# CD.net
KiCad netlist of a schematic drawn in EAGLE
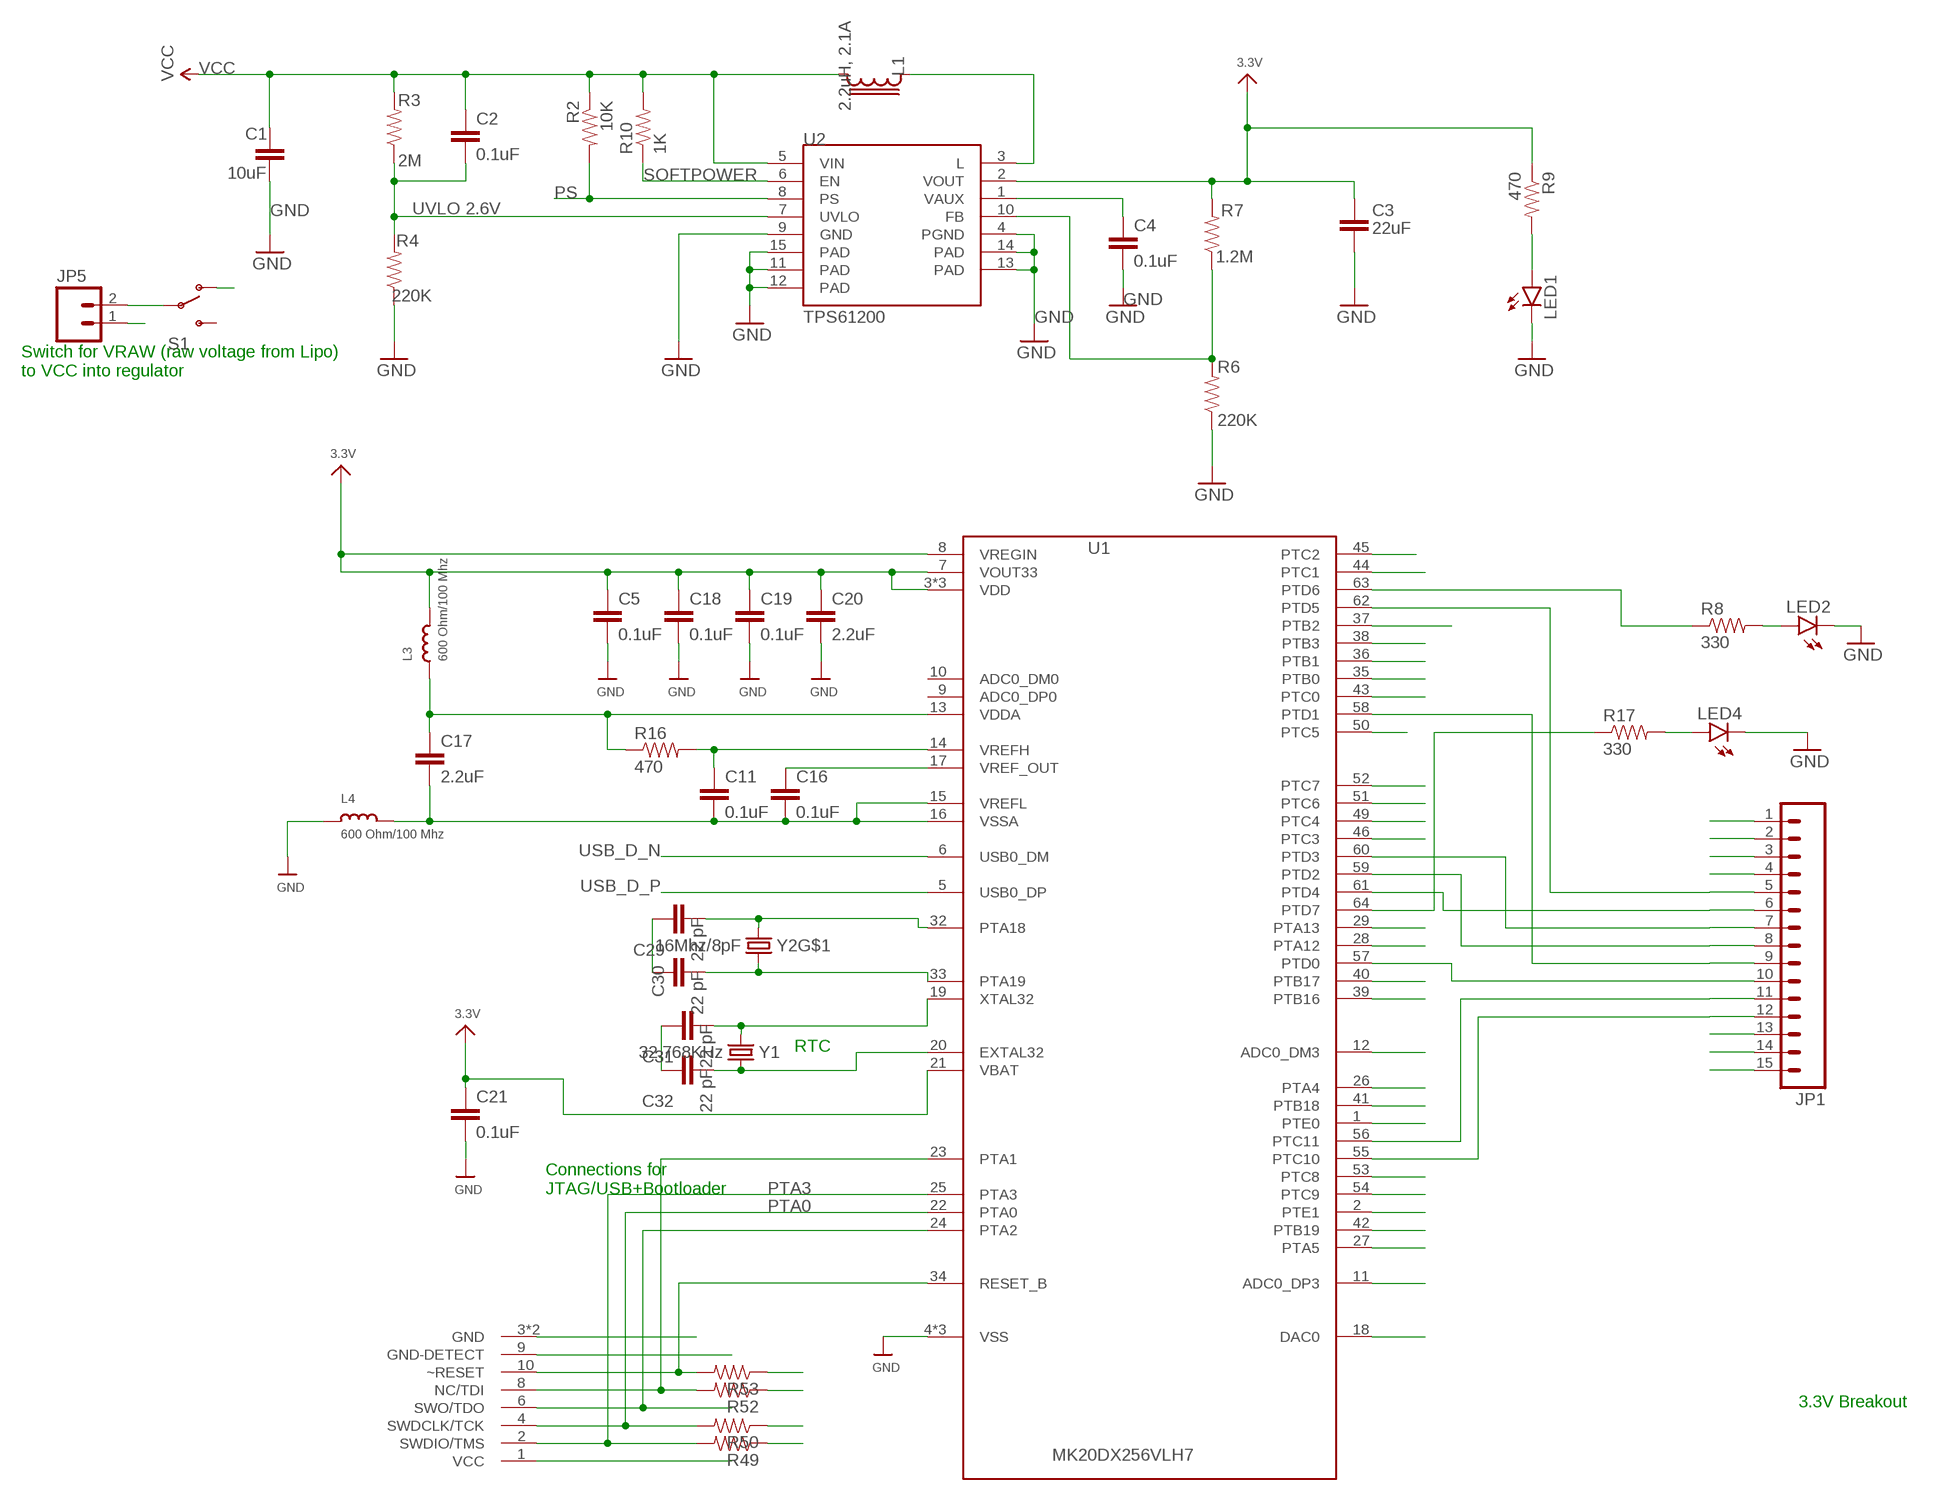
[diagram p0: schematic, sheet 1]
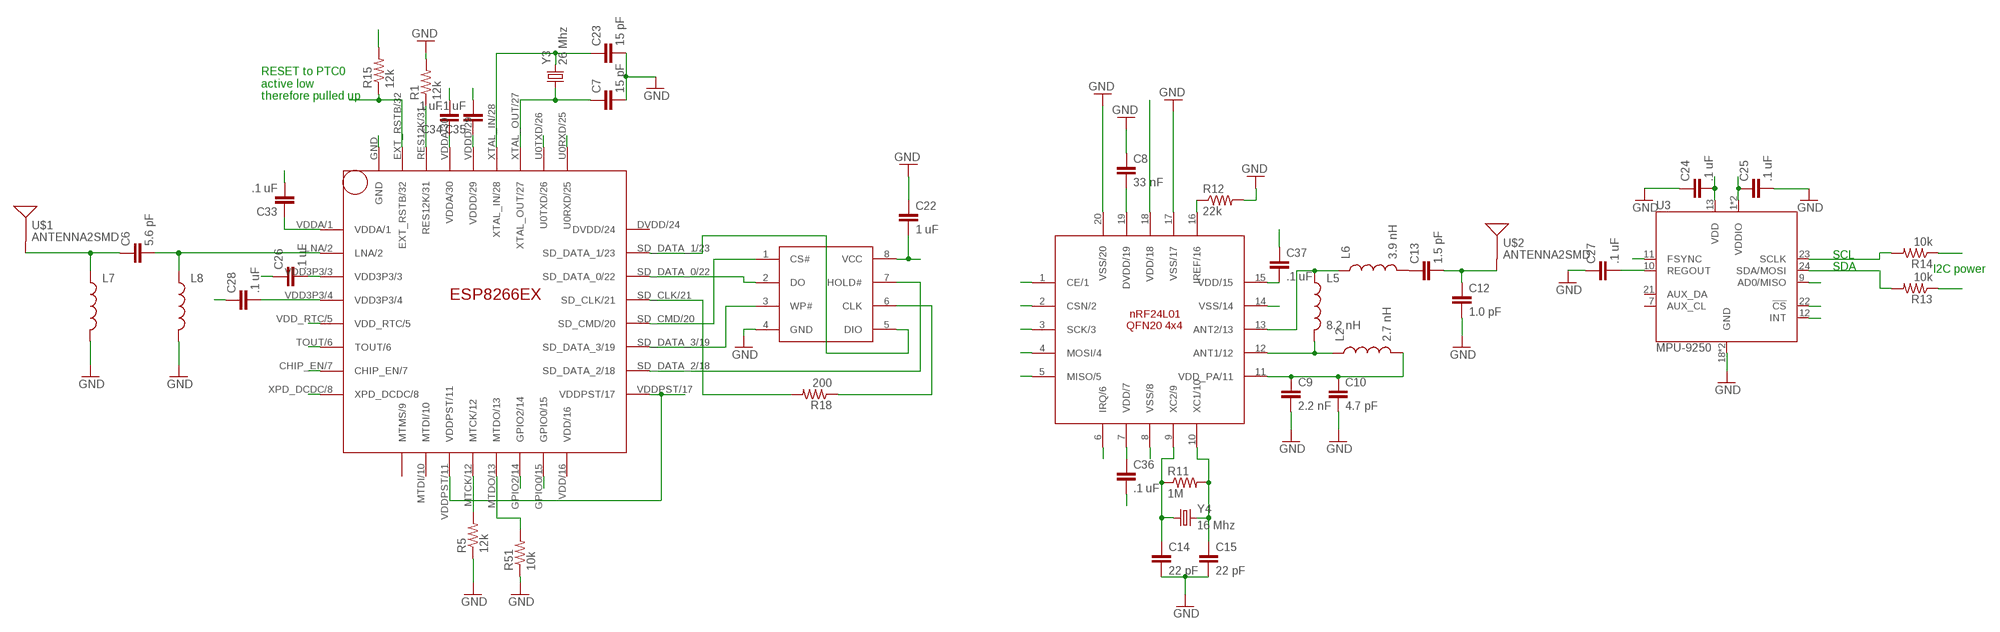
[diagram p1: schematic, sheet 2]
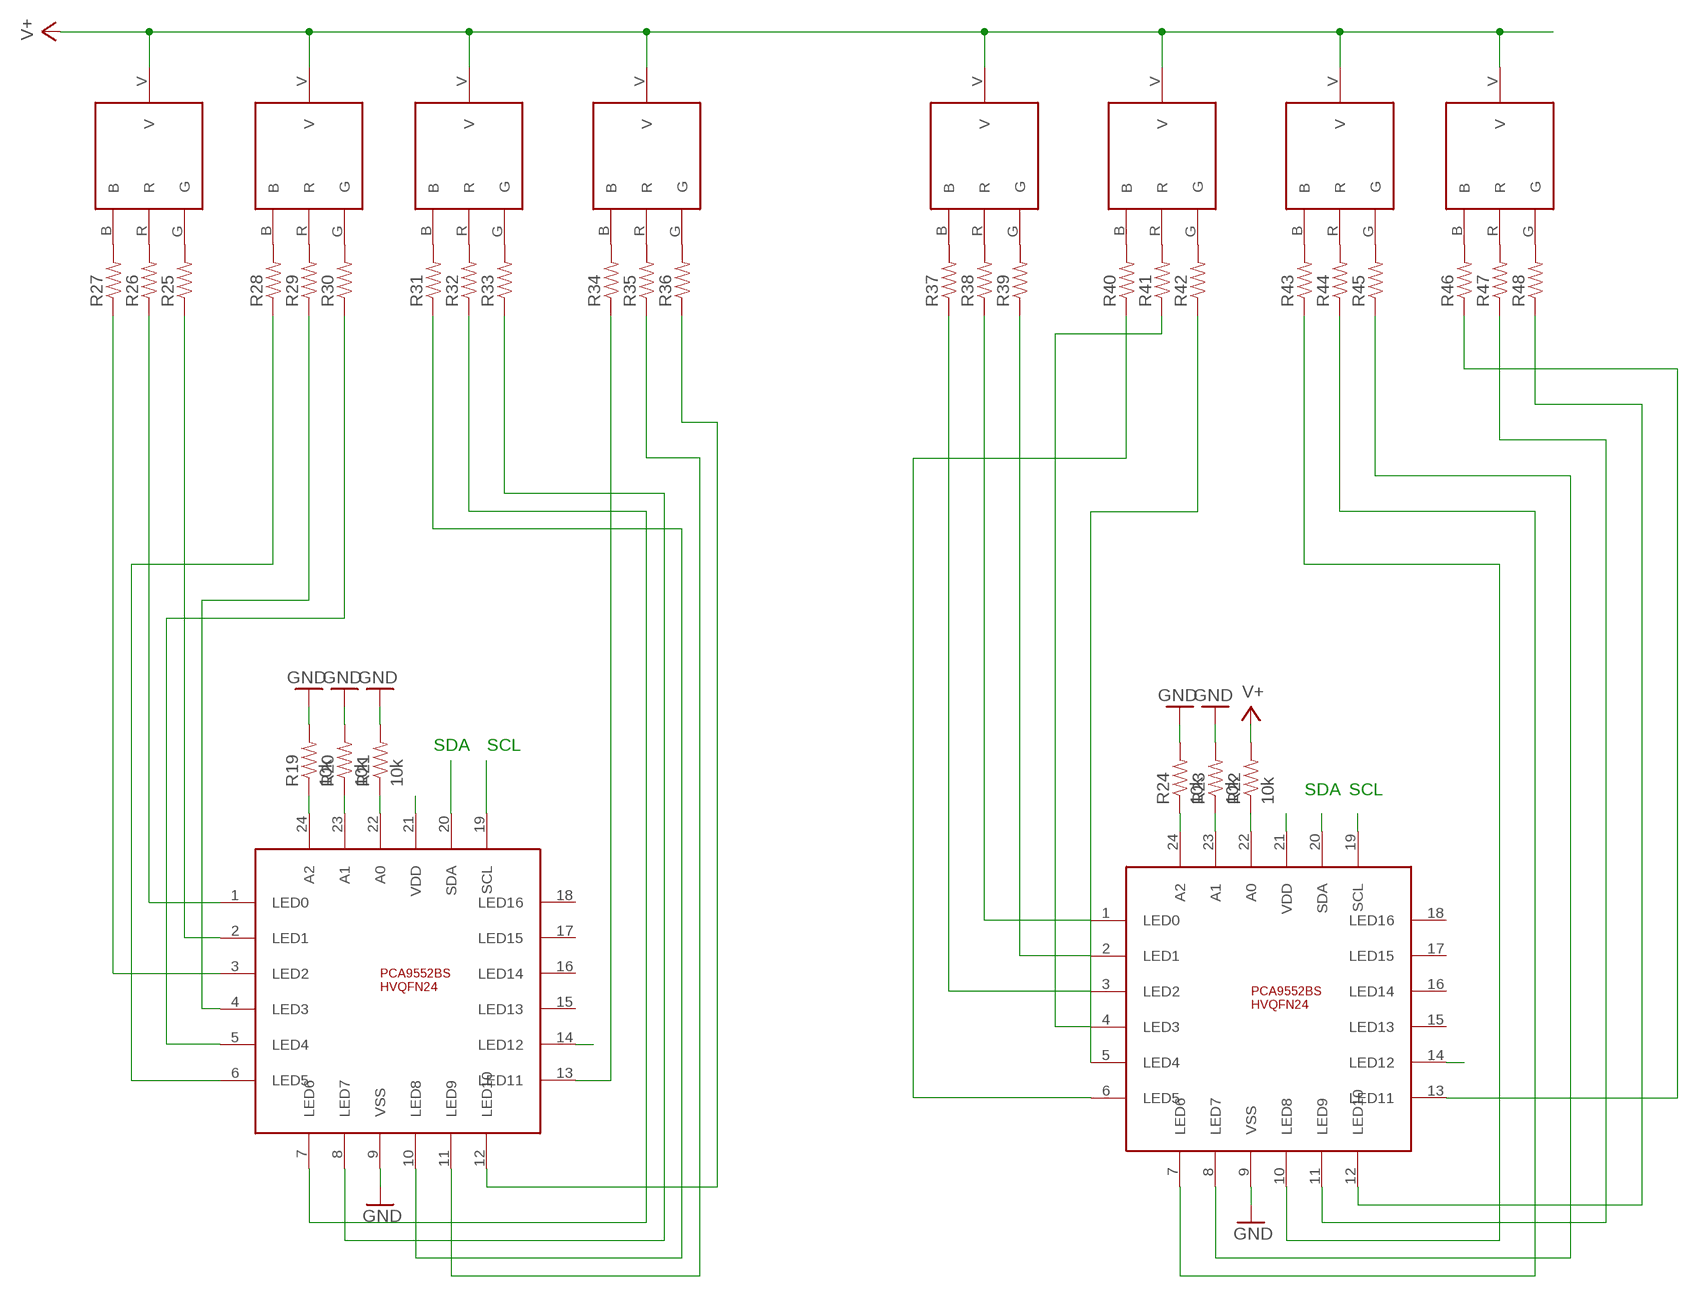
[diagram p2: schematic, sheet 3]

(export (version "E")
  (design (tool "Eeschema 10.0.6"))
  (components
    (comp (ref "C1")
      (value "10uF")
      (footprint "eagle-import:0603-CAP")
      (fields (field (name "MF") "Murata") (field (name "MPN") "GRM188R60J106ME47D"))
      (libsource (lib "eagle-import") (part "CAPACITOR-10UF"))
    )
    (comp (ref "C2")
      (value "0.1uF")
      (footprint "eagle-import:0603-CAP")
      (fields (field (name "MF") "Kemet") (field (name "MPN") "C0603C104J3RACTU"))
      (libsource (lib "eagle-import") (part "CAPACITOR-0.1UF"))
    )
    (comp (ref "C3")
      (value "22uF")
      (footprint "eagle-import:0603-CAP")
      (fields (field (name "MF") "Murata") (field (name "MPN") "GRM188R60J226MEA0D"))
      (libsource (lib "eagle-import") (part "CAPACITOR-22UF"))
    )
    (comp (ref "C4")
      (value "0.1uF")
      (footprint "eagle-import:0603-CAP")
      (fields (field (name "MF") "Kemet") (field (name "MPN") "C0603C104J3RACTU"))
      (libsource (lib "eagle-import") (part "CAPACITOR-0.1UF"))
    )
    (comp (ref "C5")
      (value "0.1uF")
      (footprint "eagle-import:0603-CAP")
      (fields (field (name "MF") "Kemet") (field (name "MPN") "C0603C104J3RACTU"))
      (libsource (lib "eagle-import") (part "CAPACITOR-0.1UF"))
    )
    (comp (ref "C11")
      (value "0.1uF")
      (footprint "eagle-import:0603-CAP")
      (fields (field (name "MF") "Kemet") (field (name "MPN") "C0603C104J3RACTU"))
      (libsource (lib "eagle-import") (part "CAPACITOR-0.1UF"))
    )
    (comp (ref "C16")
      (value "0.1uF")
      (footprint "eagle-import:0603-CAP")
      (fields (field (name "MF") "Kemet") (field (name "MPN") "C0603C104J3RACTU"))
      (libsource (lib "eagle-import") (part "CAPACITOR-0.1UF"))
    )
    (comp (ref "C17")
      (value "2.2uF")
      (footprint "eagle-import:0603-CAP")
      (fields (field (name "MF") "Kemet") (field (name "MPN") "C0603C225K4PACTU"))
      (libsource (lib "eagle-import") (part "CAPACITOR-2.2UF"))
    )
    (comp (ref "C18")
      (value "0.1uF")
      (footprint "eagle-import:0603-CAP")
      (fields (field (name "MF") "Kemet") (field (name "MPN") "C0603C104J3RACTU"))
      (libsource (lib "eagle-import") (part "CAPACITOR-0.1UF"))
    )
    (comp (ref "C19")
      (value "0.1uF")
      (footprint "eagle-import:0603-CAP")
      (fields (field (name "MF") "Kemet") (field (name "MPN") "C0603C104J3RACTU"))
      (libsource (lib "eagle-import") (part "CAPACITOR-0.1UF"))
    )
    (comp (ref "C20")
      (value "2.2uF")
      (footprint "eagle-import:0603-CAP")
      (fields (field (name "MF") "Kemet") (field (name "MPN") "C0603C225K4PACTU"))
      (libsource (lib "eagle-import") (part "CAPACITOR-2.2UF"))
    )
    (comp (ref "C21")
      (value "0.1uF")
      (footprint "eagle-import:0603-CAP")
      (fields (field (name "MF") "Kemet") (field (name "MPN") "C0603C104J3RACTU"))
      (libsource (lib "eagle-import") (part "CAPACITOR-0.1UF"))
    )
    (comp (ref "C29")
      (value "22 pF")
      (footprint "eagle-import:0603-CAP")
      (fields (field (name "MF") "Murata") (field (name "MPN") "GRM188R60J106ME47D"))
      (libsource (lib "eagle-import") (part "CAPACITOR-10UF"))
    )
    (comp (ref "C30")
      (value "22 pF")
      (footprint "eagle-import:0603-CAP")
      (fields (field (name "MF") "Murata") (field (name "MPN") "GRM188R60J106ME47D"))
      (libsource (lib "eagle-import") (part "CAPACITOR-10UF"))
    )
    (comp (ref "C31")
      (value "22 pF")
      (footprint "eagle-import:0603-CAP")
      (fields (field (name "MF") "Murata") (field (name "MPN") "GRM188R60J106ME47D"))
      (libsource (lib "eagle-import") (part "CAPACITOR-10UF"))
    )
    (comp (ref "C32")
      (value "22 pF")
      (footprint "eagle-import:0603-CAP")
      (fields (field (name "MF") "Murata") (field (name "MPN") "GRM188R60J106ME47D"))
      (libsource (lib "eagle-import") (part "CAPACITOR-10UF"))
    )
    (comp (ref "JP1")
      (value "M15")
      (footprint "eagle-import:1X15")
      (libsource (lib "eagle-import") (part "M15"))
    )
    (comp (ref "JP5")
      (value "M02PTH")
      (footprint "eagle-import:1X02")
      (libsource (lib "eagle-import") (part "M02PTH"))
    )
    (comp (ref "L1")
      (value "2.2uH, 2.1A")
      (footprint "eagle-import:LPS3015")
      (fields (field (name "MF") "Coilcraft") (field (name "MPN") "LPS3015-222MRB"))
      (libsource (lib "eagle-import") (part "LPS30152.2UH"))
    )
    (comp (ref "L3")
      (value "600 Ohm/100 Mhz")
      (footprint "eagle-import:0805")
      (fields (field (name "MF") "Taiyo Yuden") (field (name "MPN") "BK2125HM601-T"))
      (libsource (lib "eagle-import") (part "INDUCTOR-BK2125HM601-T"))
    )
    (comp (ref "L4")
      (value "600 Ohm/100 Mhz")
      (footprint "eagle-import:0805")
      (fields (field (name "MF") "Taiyo Yuden") (field (name "MPN") "BK2125HM601-T"))
      (libsource (lib "eagle-import") (part "INDUCTOR-BK2125HM601-T"))
    )
    (comp (ref "LED1")
      (value "LED-GREEN")
      (footprint "eagle-import:LED-0603")
      (fields (field (name "MF") "Avago") (field (name "MPN") "HSMG-C190"))
      (libsource (lib "eagle-import") (part "LED-GREEN"))
    )
    (comp (ref "LED2")
      (value "LED-GREEN")
      (footprint "eagle-import:LED-0603")
      (fields (field (name "MF") "Avago") (field (name "MPN") "HSMG-C190"))
      (libsource (lib "eagle-import") (part "LED-GREEN"))
    )
    (comp (ref "LED4")
      (value "LED-GREEN")
      (footprint "eagle-import:LED-0603")
      (fields (field (name "MF") "Avago") (field (name "MPN") "HSMG-C190"))
      (libsource (lib "eagle-import") (part "LED-GREEN"))
    )
    (comp (ref "R2")
      (value "10K")
      (footprint "eagle-import:0603-RES")
      (fields (field (name "MF") "Panasonic") (field (name "MPN") "ERJ-3GEYJ103V"))
      (libsource (lib "eagle-import") (part "RESISTOR-10K"))
    )
    (comp (ref "R3")
      (value "2M")
      (footprint "eagle-import:0603-RES")
      (fields (field (name "MF") "Panasonic") (field (name "MPN") "ERJ-3GEYJ205V"))
      (libsource (lib "eagle-import") (part "RESISTOR-2M"))
    )
    (comp (ref "R4")
      (value "220K")
      (footprint "eagle-import:0603-RES")
      (fields (field (name "MF") "Panasonic") (field (name "MPN") "ERJ-3GEYJ224V"))
      (libsource (lib "eagle-import") (part "RESISTOR-220K"))
    )
    (comp (ref "R6")
      (value "220K")
      (footprint "eagle-import:0603-RES")
      (fields (field (name "MF") "Panasonic") (field (name "MPN") "ERJ-3GEYJ224V"))
      (libsource (lib "eagle-import") (part "RESISTOR-220K"))
    )
    (comp (ref "R7")
      (value "1.2M")
      (footprint "eagle-import:0603-RES")
      (fields (field (name "MF") "Panasonic") (field (name "MPN") "ERJ-3GEYJ125V"))
      (libsource (lib "eagle-import") (part "RESISTOR-1.2M"))
    )
    (comp (ref "R8")
      (value "330")
      (footprint "eagle-import:0603-RES")
      (fields (field (name "MF") "Panasonic") (field (name "MPN") "ERJ-3GEYJ471V"))
      (libsource (lib "eagle-import") (part "RESISTOR-470"))
    )
    (comp (ref "R9")
      (value "470")
      (footprint "eagle-import:0603-RES")
      (fields (field (name "MF") "Panasonic") (field (name "MPN") "ERJ-3GEYJ471V"))
      (libsource (lib "eagle-import") (part "RESISTOR-470"))
    )
    (comp (ref "R10")
      (value "1K")
      (footprint "eagle-import:0603-RES")
      (fields (field (name "MF") "Panasonic") (field (name "MPN") "ERJ-3GEYJ102V"))
      (libsource (lib "eagle-import") (part "RESISTOR-1K"))
    )
    (comp (ref "R16")
      (value "470")
      (footprint "eagle-import:0603-RES")
      (fields (field (name "MF") "Panasonic") (field (name "MPN") "ERJ-3GEYJ471V"))
      (libsource (lib "eagle-import") (part "RESISTOR-470"))
    )
    (comp (ref "R17")
      (value "330")
      (footprint "eagle-import:0603-RES")
      (fields (field (name "MF") "Panasonic") (field (name "MPN") "ERJ-3GEYJ471V"))
      (libsource (lib "eagle-import") (part "RESISTOR-470"))
    )
    (comp (ref "R49")
      (value "RESISTOR0402-RES")
      (footprint "eagle-import:0402-RES")
      (libsource (lib "eagle-import") (part "RESISTOR0402-RES"))
    )
    (comp (ref "R50")
      (value "RESISTOR0402-RES")
      (footprint "eagle-import:0402-RES")
      (libsource (lib "eagle-import") (part "RESISTOR0402-RES"))
    )
    (comp (ref "R52")
      (value "RESISTOR0402-RES")
      (footprint "eagle-import:0402-RES")
      (libsource (lib "eagle-import") (part "RESISTOR0402-RES"))
    )
    (comp (ref "R53")
      (value "RESISTOR0402-RES")
      (footprint "eagle-import:0402-RES")
      (libsource (lib "eagle-import") (part "RESISTOR0402-RES"))
    )
    (comp (ref "S1")
      (value "SWITCH-SPDT-SMD-A")
      (footprint "eagle-import:SWITCH-SPST-SMD-A")
      (libsource (lib "eagle-import") (part "SWITCH-SPDT-SMD-A"))
    )
    (comp (ref "U$7")
      (value "2X5_0.05\"_CORTEX_DEBUGTH_NOKEY_UNSHROUDED")
      (footprint "eagle-import:2X5_0.05__TH_NS")
      (libsource (lib "eagle-import") (part "2X5_0.05{dblquote}_CORTEX_DEBUGTH_NOKEY_UNSHROUDED"))
    )
    (comp (ref "U1")
      (value "MK20DX256VLH7")
      (footprint "eagle-import:MK20DX256VLH7")
      (fields (field (name "MF") "Freescale"))
      (libsource (lib "eagle-import") (part "MK20DX256VLH7"))
    )
    (comp (ref "U2")
      (value "TPS61200")
      (footprint "eagle-import:QFN-10_PAD")
      (fields (field (name "MF") "Texas Instruments") (field (name "MPN") "TPS61200DRCR"))
      (libsource (lib "eagle-import") (part "TPS61200"))
    )
    (comp (ref "Y1")
      (value "32.768KHz")
      (footprint "eagle-import:CRYSTAL-TXC-7A")
      (fields (field (name "MF") "Epson Timing") (field (name "MPN") "FC-255 32.7680K-A3"))
      (libsource (lib "eagle-import") (part "CRYSTAL/32.768KHZ/SMD-TXC_7A"))
    )
    (comp (ref "Y2")
      (value "16Mhz/8pF")
      (footprint "eagle-import:CRYSTAL-SMD-5X3")
      (fields (field (name "MF") "ECS") (field (name "MPN") "ECS-160-8-30B-CKM"))
      (libsource (lib "eagle-import") (part "CRYSTAL/SMD-5X3-GND16MHZ/8PF"))
    )
    (comp (ref "R19")
      (value "10k")
      (footprint "eagle-import:0603-RES")
      (libsource (lib "eagle-import") (part "RESISTOR0603-RES"))
    )
    (comp (ref "R20")
      (value "10k")
      (footprint "eagle-import:0603-RES")
      (libsource (lib "eagle-import") (part "RESISTOR0603-RES"))
    )
    (comp (ref "R21")
      (value "10k")
      (footprint "eagle-import:0603-RES")
      (libsource (lib "eagle-import") (part "RESISTOR0603-RES"))
    )
    (comp (ref "R22")
      (value "10k")
      (footprint "eagle-import:0603-RES")
      (libsource (lib "eagle-import") (part "RESISTOR0603-RES"))
    )
    (comp (ref "R23")
      (value "10k")
      (footprint "eagle-import:0603-RES")
      (libsource (lib "eagle-import") (part "RESISTOR0603-RES"))
    )
    (comp (ref "R24")
      (value "10k")
      (footprint "eagle-import:0603-RES")
      (libsource (lib "eagle-import") (part "RESISTOR0603-RES"))
    )
    (comp (ref "R25")
      (value "RESISTOR0402-RES")
      (footprint "eagle-import:0402-RES")
      (libsource (lib "eagle-import") (part "RESISTOR0402-RES"))
    )
    (comp (ref "R26")
      (value "RESISTOR0402-RES")
      (footprint "eagle-import:0402-RES")
      (libsource (lib "eagle-import") (part "RESISTOR0402-RES"))
    )
    (comp (ref "R27")
      (value "RESISTOR0402-RES")
      (footprint "eagle-import:0402-RES")
      (libsource (lib "eagle-import") (part "RESISTOR0402-RES"))
    )
    (comp (ref "R28")
      (value "RESISTOR0402-RES")
      (footprint "eagle-import:0402-RES")
      (libsource (lib "eagle-import") (part "RESISTOR0402-RES"))
    )
    (comp (ref "R29")
      (value "RESISTOR0402-RES")
      (footprint "eagle-import:0402-RES")
      (libsource (lib "eagle-import") (part "RESISTOR0402-RES"))
    )
    (comp (ref "R30")
      (value "RESISTOR0402-RES")
      (footprint "eagle-import:0402-RES")
      (libsource (lib "eagle-import") (part "RESISTOR0402-RES"))
    )
    (comp (ref "R31")
      (value "RESISTOR0402-RES")
      (footprint "eagle-import:0402-RES")
      (libsource (lib "eagle-import") (part "RESISTOR0402-RES"))
    )
    (comp (ref "R32")
      (value "RESISTOR0402-RES")
      (footprint "eagle-import:0402-RES")
      (libsource (lib "eagle-import") (part "RESISTOR0402-RES"))
    )
    (comp (ref "R33")
      (value "RESISTOR0402-RES")
      (footprint "eagle-import:0402-RES")
      (libsource (lib "eagle-import") (part "RESISTOR0402-RES"))
    )
    (comp (ref "R34")
      (value "RESISTOR0402-RES")
      (footprint "eagle-import:0402-RES")
      (libsource (lib "eagle-import") (part "RESISTOR0402-RES"))
    )
    (comp (ref "R35")
      (value "RESISTOR0402-RES")
      (footprint "eagle-import:0402-RES")
      (libsource (lib "eagle-import") (part "RESISTOR0402-RES"))
    )
    (comp (ref "R36")
      (value "RESISTOR0402-RES")
      (footprint "eagle-import:0402-RES")
      (libsource (lib "eagle-import") (part "RESISTOR0402-RES"))
    )
    (comp (ref "R37")
      (value "RESISTOR0402-RES")
      (footprint "eagle-import:0402-RES")
      (libsource (lib "eagle-import") (part "RESISTOR0402-RES"))
    )
    (comp (ref "R38")
      (value "RESISTOR0402-RES")
      (footprint "eagle-import:0402-RES")
      (libsource (lib "eagle-import") (part "RESISTOR0402-RES"))
    )
    (comp (ref "R39")
      (value "RESISTOR0402-RES")
      (footprint "eagle-import:0402-RES")
      (libsource (lib "eagle-import") (part "RESISTOR0402-RES"))
    )
    (comp (ref "R40")
      (value "RESISTOR0402-RES")
      (footprint "eagle-import:0402-RES")
      (libsource (lib "eagle-import") (part "RESISTOR0402-RES"))
    )
    (comp (ref "R41")
      (value "RESISTOR0402-RES")
      (footprint "eagle-import:0402-RES")
      (libsource (lib "eagle-import") (part "RESISTOR0402-RES"))
    )
    (comp (ref "R42")
      (value "RESISTOR0402-RES")
      (footprint "eagle-import:0402-RES")
      (libsource (lib "eagle-import") (part "RESISTOR0402-RES"))
    )
    (comp (ref "R43")
      (value "RESISTOR0402-RES")
      (footprint "eagle-import:0402-RES")
      (libsource (lib "eagle-import") (part "RESISTOR0402-RES"))
    )
    (comp (ref "R44")
      (value "RESISTOR0402-RES")
      (footprint "eagle-import:0402-RES")
      (libsource (lib "eagle-import") (part "RESISTOR0402-RES"))
    )
    (comp (ref "R45")
      (value "RESISTOR0402-RES")
      (footprint "eagle-import:0402-RES")
      (libsource (lib "eagle-import") (part "RESISTOR0402-RES"))
    )
    (comp (ref "R46")
      (value "RESISTOR0402-RES")
      (footprint "eagle-import:0402-RES")
      (libsource (lib "eagle-import") (part "RESISTOR0402-RES"))
    )
    (comp (ref "R47")
      (value "RESISTOR0402-RES")
      (footprint "eagle-import:0402-RES")
      (libsource (lib "eagle-import") (part "RESISTOR0402-RES"))
    )
    (comp (ref "R48")
      (value "RESISTOR0402-RES")
      (footprint "eagle-import:0402-RES")
      (libsource (lib "eagle-import") (part "RESISTOR0402-RES"))
    )
    (comp (ref "U$8")
      (value "LTST-C19FD1WT")
      (footprint "eagle-import:LTST-C19FD1WT")
      (libsource (lib "eagle-import") (part "LTST-C19FD1WT"))
    )
    (comp (ref "U$11")
      (value "LTST-C19FD1WT")
      (footprint "eagle-import:LTST-C19FD1WT")
      (libsource (lib "eagle-import") (part "LTST-C19FD1WT"))
    )
    (comp (ref "U$13")
      (value "LTST-C19FD1WT")
      (footprint "eagle-import:LTST-C19FD1WT")
      (libsource (lib "eagle-import") (part "LTST-C19FD1WT"))
    )
    (comp (ref "U$14")
      (value "LTST-C19FD1WT")
      (footprint "eagle-import:LTST-C19FD1WT")
      (libsource (lib "eagle-import") (part "LTST-C19FD1WT"))
    )
    (comp (ref "U$15")
      (value "LTST-C19FD1WT")
      (footprint "eagle-import:LTST-C19FD1WT")
      (libsource (lib "eagle-import") (part "LTST-C19FD1WT"))
    )
    (comp (ref "U$16")
      (value "LTST-C19FD1WT")
      (footprint "eagle-import:LTST-C19FD1WT")
      (libsource (lib "eagle-import") (part "LTST-C19FD1WT"))
    )
    (comp (ref "U$17")
      (value "LTST-C19FD1WT")
      (footprint "eagle-import:LTST-C19FD1WT")
      (libsource (lib "eagle-import") (part "LTST-C19FD1WT"))
    )
    (comp (ref "U$18")
      (value "LTST-C19FD1WT")
      (footprint "eagle-import:LTST-C19FD1WT")
      (libsource (lib "eagle-import") (part "LTST-C19FD1WT"))
    )
    (comp (ref "U$20")
      (value "PCA9552BS")
      (footprint "eagle-import:HVQFN24")
      (libsource (lib "eagle-import") (part "PCA9552BS"))
    )
    (comp (ref "U$21")
      (value "PCA9552BS")
      (footprint "eagle-import:HVQFN24")
      (libsource (lib "eagle-import") (part "PCA9552BS"))
    )
    (comp (ref "C6")
      (value "5.6 pF")
      (footprint "eagle-import:0603-CAP")
      (libsource (lib "eagle-import") (part "CAP0603-CAP"))
    )
    (comp (ref "C7")
      (value "15 pF")
      (footprint "eagle-import:0603-CAP")
      (libsource (lib "eagle-import") (part "CAP0603-CAP"))
    )
    (comp (ref "C8")
      (value "33 nF")
      (footprint "eagle-import:0603-CAP")
      (libsource (lib "eagle-import") (part "CAP0603-CAP"))
    )
    (comp (ref "C9")
      (value "2.2 nF")
      (footprint "eagle-import:0603-CAP")
      (libsource (lib "eagle-import") (part "CAP0603-CAP"))
    )
    (comp (ref "C10")
      (value "4.7 pF")
      (footprint "eagle-import:0603-CAP")
      (libsource (lib "eagle-import") (part "CAP0603-CAP"))
    )
    (comp (ref "C12")
      (value "1.0 pF")
      (footprint "eagle-import:0603-CAP")
      (libsource (lib "eagle-import") (part "CAP0603-CAP"))
    )
    (comp (ref "C13")
      (value "1.5 pF")
      (footprint "eagle-import:0603-CAP")
      (libsource (lib "eagle-import") (part "CAP0603-CAP"))
    )
    (comp (ref "C14")
      (value "22 pF")
      (footprint "eagle-import:0603-CAP")
      (libsource (lib "eagle-import") (part "CAP0603-CAP"))
    )
    (comp (ref "C15")
      (value "22 pF")
      (footprint "eagle-import:0603-CAP")
      (libsource (lib "eagle-import") (part "CAP0603-CAP"))
    )
    (comp (ref "C22")
      (value "1 uF")
      (footprint "eagle-import:0603-CAP")
      (libsource (lib "eagle-import") (part "CAP0603-CAP"))
    )
    (comp (ref "C23")
      (value "15 pF")
      (footprint "eagle-import:0603-CAP")
      (libsource (lib "eagle-import") (part "CAP0603-CAP"))
    )
    (comp (ref "C24")
      (value ".1 uF")
      (footprint "eagle-import:0603-CAP")
      (libsource (lib "eagle-import") (part "CAP0603-CAP"))
    )
    (comp (ref "C25")
      (value ".1 uF")
      (footprint "eagle-import:0603-CAP")
      (libsource (lib "eagle-import") (part "CAP0603-CAP"))
    )
    (comp (ref "C26")
      (value ".1 uF")
      (footprint "eagle-import:0603-CAP")
      (libsource (lib "eagle-import") (part "CAP0603-CAP"))
    )
    (comp (ref "C27")
      (value ".1 uF")
      (footprint "eagle-import:0603-CAP")
      (libsource (lib "eagle-import") (part "CAP0603-CAP"))
    )
    (comp (ref "C28")
      (value ".1 uF")
      (footprint "eagle-import:0603-CAP")
      (libsource (lib "eagle-import") (part "CAP0603-CAP"))
    )
    (comp (ref "C33")
      (value ".1 uF")
      (footprint "eagle-import:0603-CAP")
      (libsource (lib "eagle-import") (part "CAP0603-CAP"))
    )
    (comp (ref "C34")
      (value ".1 uF")
      (footprint "eagle-import:0603-CAP")
      (libsource (lib "eagle-import") (part "CAP0603-CAP"))
    )
    (comp (ref "C35")
      (value ".1 uF")
      (footprint "eagle-import:0603-CAP")
      (libsource (lib "eagle-import") (part "CAP0603-CAP"))
    )
    (comp (ref "C36")
      (value ".1 uF")
      (footprint "eagle-import:0603-CAP")
      (libsource (lib "eagle-import") (part "CAP0603-CAP"))
    )
    (comp (ref "C37")
      (value ".1 uF")
      (footprint "eagle-import:0603-CAP")
      (libsource (lib "eagle-import") (part "CAP0603-CAP"))
    )
    (comp (ref "L2")
      (value "2.7 nH")
      (footprint "eagle-import:C0402")
      (libsource (lib "eagle-import") (part "INDUCTOR0402"))
    )
    (comp (ref "L5")
      (value "8.2 nH")
      (footprint "eagle-import:C0402")
      (libsource (lib "eagle-import") (part "INDUCTOR0402"))
    )
    (comp (ref "L6")
      (value "3.9 nH")
      (footprint "eagle-import:C0402")
      (libsource (lib "eagle-import") (part "INDUCTOR0402"))
    )
    (comp (ref "L7")
      (value "INDUCTOR30OHM,1.8A")
      (footprint "eagle-import:0603")
      (libsource (lib "eagle-import") (part "INDUCTOR30OHM,1.8A"))
    )
    (comp (ref "L8")
      (value "INDUCTOR30OHM,1.8A")
      (footprint "eagle-import:0603")
      (libsource (lib "eagle-import") (part "INDUCTOR30OHM,1.8A"))
    )
    (comp (ref "R1")
      (value "12k")
      (footprint "eagle-import:0603-RES")
      (libsource (lib "eagle-import") (part "SparkFun-Resistors_RESISTOR0603-RES"))
    )
    (comp (ref "R5")
      (value "12k")
      (footprint "eagle-import:0603-RES")
      (libsource (lib "eagle-import") (part "SparkFun-Resistors_RESISTOR0603-RES"))
    )
    (comp (ref "R11")
      (value "1M")
      (footprint "eagle-import:0603-RES")
      (libsource (lib "eagle-import") (part "SparkFun-Resistors_RESISTOR0603-RES"))
    )
    (comp (ref "R12")
      (value "22k")
      (footprint "eagle-import:0603-RES")
      (libsource (lib "eagle-import") (part "SparkFun-Resistors_RESISTOR0603-RES"))
    )
    (comp (ref "R13")
      (value "10k")
      (footprint "eagle-import:0603-RES")
      (libsource (lib "eagle-import") (part "SparkFun-Resistors_RESISTOR0603-RES"))
    )
    (comp (ref "R14")
      (value "10k")
      (footprint "eagle-import:0603-RES")
      (libsource (lib "eagle-import") (part "SparkFun-Resistors_RESISTOR0603-RES"))
    )
    (comp (ref "R15")
      (value "12k")
      (footprint "eagle-import:0603-RES")
      (libsource (lib "eagle-import") (part "SparkFun-Resistors_RESISTOR0603-RES"))
    )
    (comp (ref "R18")
      (value "200")
      (footprint "eagle-import:0603-RES")
      (libsource (lib "eagle-import") (part "SparkFun-Resistors_RESISTOR0603-RES"))
    )
    (comp (ref "R51")
      (value "10k")
      (footprint "eagle-import:0603-RES")
      (libsource (lib "eagle-import") (part "SparkFun-Resistors_RESISTOR0603-RES"))
    )
    (comp (ref "U$1")
      (value "ANTENNA2SMD")
      (footprint "eagle-import:ANTENNA-CHIP2")
      (libsource (lib "eagle-import") (part "ANTENNA2SMD"))
    )
    (comp (ref "U$2")
      (value "ANTENNA2SMD")
      (footprint "eagle-import:ANTENNA-CHIP2")
      (libsource (lib "eagle-import") (part "ANTENNA2SMD"))
    )
    (comp (ref "U$3")
      (value "25Q40")
      (footprint "eagle-import:SOP8")
      (libsource (lib "eagle-import") (part "25Q40"))
    )
    (comp (ref "U$4")
      (value "NRF24L01")
      (footprint "eagle-import:QFN20(4X4)")
      (libsource (lib "eagle-import") (part "NRF24L01"))
    )
    (comp (ref "U$6")
      (value "ESP8266EX")
      (footprint "eagle-import:QFN32")
      (libsource (lib "eagle-import") (part "ESP8266EX"))
    )
    (comp (ref "U3")
      (value "MPU-9250")
      (footprint "eagle-import:QFN-24_3MM")
      (libsource (lib "eagle-import") (part "MPU-9250"))
    )
    (comp (ref "Y3")
      (value "26 Mhz")
      (footprint "eagle-import:CRYSTAL-SMD-5X3")
      (libsource (lib "eagle-import") (part "CRYSTAL5X3"))
    )
    (comp (ref "Y4")
      (value "16 Mhz")
      (footprint "eagle-import:CRYSTAL-SMD-5X3")
      (libsource (lib "eagle-import") (part "CRYSTAL5X3"))
    )
  )
  (nets
    (net (code "1") (name "3.3V") (class "Default")
      (node (ref "C18") (pin "1") (pinfunction "1_1") (pintype "passive"))
      (node (ref "C19") (pin "1") (pinfunction "1_1") (pintype "passive"))
      (node (ref "C20") (pin "1") (pinfunction "1_1") (pintype "passive"))
      (node (ref "C21") (pin "1") (pinfunction "1_1") (pintype "passive"))
      (node (ref "C22") (pin "2") (pinfunction "2_2") (pintype "passive"))
      (node (ref "C24") (pin "2") (pinfunction "2_2") (pintype "passive"))
      (node (ref "C25") (pin "1") (pinfunction "1_1") (pintype "passive"))
      (node (ref "C26") (pin "2") (pinfunction "2_2") (pintype "passive"))
      (node (ref "C28") (pin "2") (pinfunction "2_2") (pintype "passive"))
      (node (ref "C3") (pin "1") (pinfunction "1_1") (pintype "passive"))
      (node (ref "C33") (pin "1") (pinfunction "1_1") (pintype "passive"))
      (node (ref "C34") (pin "1") (pinfunction "1_1") (pintype "passive"))
      (node (ref "C35") (pin "1") (pinfunction "1_1") (pintype "passive"))
      (node (ref "C36") (pin "1") (pinfunction "1_1") (pintype "passive"))
      (node (ref "C37") (pin "2") (pinfunction "2_2") (pintype "passive"))
      (node (ref "C5") (pin "1") (pinfunction "1_1") (pintype "passive"))
      (node (ref "JP1") (pin "13") (pinfunction "13_13") (pintype "passive"))
      (node (ref "JP1") (pin "14") (pinfunction "14_14") (pintype "passive"))
      (node (ref "JP1") (pin "15") (pinfunction "15_15") (pintype "passive"))
      (node (ref "L3") (pin "2") (pinfunction "2_2") (pintype "passive"))
      (node (ref "R13") (pin "1") (pinfunction "1_1") (pintype "passive"))
      (node (ref "R14") (pin "1") (pinfunction "1_1") (pintype "passive"))
      (node (ref "R15") (pin "2") (pinfunction "2_2") (pintype "passive"))
      (node (ref "R22") (pin "2") (pinfunction "2_2") (pintype "passive"))
      (node (ref "R49") (pin "1") (pinfunction "1_1") (pintype "passive"))
      (node (ref "R52") (pin "1") (pinfunction "1_1") (pintype "passive"))
      (node (ref "R53") (pin "1") (pinfunction "1_1") (pintype "passive"))
      (node (ref "R7") (pin "2") (pinfunction "2_2") (pintype "passive"))
      (node (ref "R9") (pin "1") (pinfunction "1_1") (pintype "passive"))
      (node (ref "U$11") (pin "V") (pinfunction "V_V") (pintype "bidirectional"))
      (node (ref "U$13") (pin "V") (pinfunction "V_V") (pintype "bidirectional"))
      (node (ref "U$14") (pin "V") (pinfunction "V_V") (pintype "bidirectional"))
      (node (ref "U$15") (pin "V") (pinfunction "V_V") (pintype "bidirectional"))
      (node (ref "U$16") (pin "V") (pinfunction "V_V") (pintype "bidirectional"))
      (node (ref "U$17") (pin "V") (pinfunction "V_V") (pintype "bidirectional"))
      (node (ref "U$18") (pin "V") (pinfunction "V_V") (pintype "bidirectional"))
      (node (ref "U$20") (pin "21") (pinfunction "VDD_21") (pintype "bidirectional"))
      (node (ref "U$21") (pin "21") (pinfunction "VDD_21") (pintype "bidirectional"))
      (node (ref "U$3") (pin "8") (pinfunction "VCC_8") (pintype "bidirectional"))
      (node (ref "U$4") (pin "15") (pinfunction "VDD/15_15") (pintype "bidirectional"))
      (node (ref "U$4") (pin "18") (pinfunction "VDD/18_18") (pintype "bidirectional"))
      (node (ref "U$4") (pin "7") (pinfunction "VDD/7_7") (pintype "bidirectional"))
      (node (ref "U$6") (pin "VDD3P3/3") (pinfunction "VDD3P3/3_VDD3P3/3") (pintype "bidirectional"))
      (node (ref "U$6") (pin "VDD3P3/4") (pinfunction "VDD3P3/4_VDD3P3/4") (pintype "bidirectional"))
      (node (ref "U$6") (pin "VDDA/1") (pinfunction "VDDA/1_VDDA/1") (pintype "bidirectional"))
      (node (ref "U$6") (pin "VDDA/30") (pinfunction "VDDA/30_VDDA/30") (pintype "bidirectional"))
      (node (ref "U$6") (pin "VDDD/29") (pinfunction "VDDD/29_VDDD/29") (pintype "bidirectional"))
      (node (ref "U$6") (pin "VDDPST/11") (pinfunction "VDDPST/11_VDDPST/11") (pintype "bidirectional"))
      (node (ref "U$6") (pin "VDDPST/17") (pinfunction "VDDPST/17_VDDPST/17") (pintype "bidirectional"))
      (node (ref "U$7") (pin "1") (pinfunction "VCC_1") (pintype "bidirectional"))
      (node (ref "U$8") (pin "V") (pinfunction "V_V") (pintype "bidirectional"))
      (node (ref "U1") (pin "21") (pinfunction "VBAT_21") (pintype "bidirectional"))
      (node (ref "U1") (pin "3") (pinfunction "VDD_3") (pintype "bidirectional"))
      (node (ref "U1") (pin "30") (pinfunction "VDD_30") (pintype "bidirectional"))
      (node (ref "U1") (pin "48") (pinfunction "VDD_48") (pintype "bidirectional"))
      (node (ref "U1") (pin "7") (pinfunction "VOUT33_7") (pintype "bidirectional"))
      (node (ref "U1") (pin "8") (pinfunction "VREGIN_8") (pintype "bidirectional"))
      (node (ref "U2") (pin "2") (pinfunction "VOUT_2") (pintype "passive"))
      (node (ref "U3") (pin "1") (pinfunction "VDDIO_1") (pintype "bidirectional"))
      (node (ref "U3") (pin "13") (pinfunction "VDD_13") (pintype "bidirectional"))
      (node (ref "U3") (pin "22") (pinfunction "~{CS}_22") (pintype "bidirectional"))
      (node (ref "U3") (pin "8") (pinfunction "VDDIO_8") (pintype "bidirectional"))
    )
    (net (code "2") (name "AD0") (class "Default")
      (node (ref "U1") (pin "45") (pinfunction "PTC2_45") (pintype "bidirectional"))
      (node (ref "U3") (pin "9") (pinfunction "AD0/MISO_9") (pintype "bidirectional"))
    )
    (net (code "3") (name "GND") (class "Default")
      (node (ref "C1") (pin "2") (pinfunction "2_2") (pintype "passive"))
      (node (ref "C10") (pin "2") (pinfunction "2_2") (pintype "passive"))
      (node (ref "C12") (pin "2") (pinfunction "2_2") (pintype "passive"))
      (node (ref "C14") (pin "2") (pinfunction "2_2") (pintype "passive"))
      (node (ref "C15") (pin "2") (pinfunction "2_2") (pintype "passive"))
      (node (ref "C18") (pin "2") (pinfunction "2_2") (pintype "passive"))
      (node (ref "C19") (pin "2") (pinfunction "2_2") (pintype "passive"))
      (node (ref "C20") (pin "2") (pinfunction "2_2") (pintype "passive"))
      (node (ref "C21") (pin "2") (pinfunction "2_2") (pintype "passive"))
      (node (ref "C22") (pin "1") (pinfunction "1_1") (pintype "passive"))
      (node (ref "C23") (pin "2") (pinfunction "2_2") (pintype "passive"))
      (node (ref "C24") (pin "1") (pinfunction "1_1") (pintype "passive"))
      (node (ref "C25") (pin "2") (pinfunction "2_2") (pintype "passive"))
      (node (ref "C26") (pin "1") (pinfunction "1_1") (pintype "passive"))
      (node (ref "C27") (pin "1") (pinfunction "1_1") (pintype "passive"))
      (node (ref "C28") (pin "1") (pinfunction "1_1") (pintype "passive"))
      (node (ref "C29") (pin "1") (pinfunction "1_1") (pintype "passive"))
      (node (ref "C3") (pin "2") (pinfunction "2_2") (pintype "passive"))
      (node (ref "C30") (pin "1") (pinfunction "1_1") (pintype "passive"))
      (node (ref "C31") (pin "1") (pinfunction "1_1") (pintype "passive"))
      (node (ref "C32") (pin "1") (pinfunction "1_1") (pintype "passive"))
      (node (ref "C33") (pin "2") (pinfunction "2_2") (pintype "passive"))
      (node (ref "C34") (pin "2") (pinfunction "2_2") (pintype "passive"))
      (node (ref "C35") (pin "2") (pinfunction "2_2") (pintype "passive"))
      (node (ref "C36") (pin "2") (pinfunction "2_2") (pintype "passive"))
      (node (ref "C37") (pin "1") (pinfunction "1_1") (pintype "passive"))
      (node (ref "C4") (pin "2") (pinfunction "2_2") (pintype "passive"))
      (node (ref "C5") (pin "2") (pinfunction "2_2") (pintype "passive"))
      (node (ref "C7") (pin "2") (pinfunction "2_2") (pintype "passive"))
      (node (ref "C8") (pin "1") (pinfunction "1_1") (pintype "passive"))
      (node (ref "C9") (pin "2") (pinfunction "2_2") (pintype "passive"))
      (node (ref "JP1") (pin "1") (pinfunction "1_1") (pintype "passive"))
      (node (ref "JP1") (pin "2") (pinfunction "2_2") (pintype "passive"))
      (node (ref "JP1") (pin "3") (pinfunction "3_3") (pintype "passive"))
      (node (ref "JP1") (pin "4") (pinfunction "4_4") (pintype "passive"))
      (node (ref "JP5") (pin "1") (pinfunction "1_1") (pintype "passive"))
      (node (ref "L4") (pin "1") (pinfunction "1_1") (pintype "passive"))
      (node (ref "L7") (pin "2") (pinfunction "2_2") (pintype "passive"))
      (node (ref "L8") (pin "2") (pinfunction "2_2") (pintype "passive"))
      (node (ref "LED1") (pin "C") (pinfunction "C_C") (pintype "passive"))
      (node (ref "LED2") (pin "C") (pinfunction "C_C") (pintype "passive"))
      (node (ref "LED4") (pin "C") (pinfunction "C_C") (pintype "passive"))
      (node (ref "R1") (pin "2") (pinfunction "2_2") (pintype "passive"))
      (node (ref "R12") (pin "2") (pinfunction "2_2") (pintype "passive"))
      (node (ref "R19") (pin "2") (pinfunction "2_2") (pintype "passive"))
      (node (ref "R20") (pin "2") (pinfunction "2_2") (pintype "passive"))
      (node (ref "R21") (pin "2") (pinfunction "2_2") (pintype "passive"))
      (node (ref "R23") (pin "2") (pinfunction "2_2") (pintype "passive"))
      (node (ref "R24") (pin "2") (pinfunction "2_2") (pintype "passive"))
      (node (ref "R4") (pin "1") (pinfunction "1_1") (pintype "passive"))
      (node (ref "R5") (pin "1") (pinfunction "1_1") (pintype "passive"))
      (node (ref "R50") (pin "1") (pinfunction "1_1") (pintype "passive"))
      (node (ref "R51") (pin "1") (pinfunction "1_1") (pintype "passive"))
      (node (ref "R6") (pin "1") (pinfunction "1_1") (pintype "passive"))
      (node (ref "U$20") (pin "9") (pinfunction "VSS_9") (pintype "bidirectional"))
      (node (ref "U$21") (pin "9") (pinfunction "VSS_9") (pintype "bidirectional"))
      (node (ref "U$3") (pin "4") (pinfunction "GND_4") (pintype "bidirectional"))
      (node (ref "U$4") (pin "14") (pinfunction "VSS/14_14") (pintype "bidirectional"))
      (node (ref "U$4") (pin "17") (pinfunction "VSS/17_17") (pintype "bidirectional"))
      (node (ref "U$4") (pin "20") (pinfunction "VSS/20_20") (pintype "bidirectional"))
      (node (ref "U$4") (pin "8") (pinfunction "VSS/8_8") (pintype "bidirectional"))
      (node (ref "U$6") (pin "GND") (pinfunction "GND_GND") (pintype "bidirectional"))
      (node (ref "U$7") (pin "3") (pinfunction "GND_3") (pintype "bidirectional"))
      (node (ref "U$7") (pin "5") (pinfunction "GND_5") (pintype "bidirectional"))
      (node (ref "U$7") (pin "9") (pinfunction "GND-DETECT_9") (pintype "bidirectional"))
      (node (ref "U1") (pin "31") (pinfunction "VSS_31") (pintype "bidirectional"))
      (node (ref "U1") (pin "4") (pinfunction "VSS_4") (pintype "bidirectional"))
      (node (ref "U1") (pin "47") (pinfunction "VSS_47") (pintype "bidirectional"))
      (node (ref "U2") (pin "11") (pinfunction "PAD_11") (pintype "power_in"))
      (node (ref "U2") (pin "12") (pinfunction "PAD_12") (pintype "power_in"))
      (node (ref "U2") (pin "13") (pinfunction "PAD_13") (pintype "power_in"))
      (node (ref "U2") (pin "14") (pinfunction "PAD_14") (pintype "power_in"))
      (node (ref "U2") (pin "15") (pinfunction "PAD_15") (pintype "power_in"))
      (node (ref "U2") (pin "4") (pinfunction "PGND_4") (pintype "power_in"))
      (node (ref "U2") (pin "9") (pinfunction "GND_9") (pintype "power_in"))
      (node (ref "U3") (pin "18") (pinfunction "GND_18") (pintype "bidirectional"))
      (node (ref "U3") (pin "20") (pinfunction "GND_20") (pintype "bidirectional"))
    )
    (net (code "4") (name "Net-(C6-Pad2)") (class "Default")
      (node (ref "C6") (pin "2") (pinfunction "2_2") (pintype "passive"))
      (node (ref "L8") (pin "1") (pinfunction "1_1") (pintype "passive"))
      (node (ref "U$6") (pin "LNA/2") (pinfunction "LNA/2_LNA/2") (pintype "bidirectional"))
    )
    (net (code "5") (name "Net-(C7-Pad1)") (class "Default")
      (node (ref "C7") (pin "1") (pinfunction "1_1") (pintype "passive"))
      (node (ref "U$6") (pin "XTAL_OUT/27") (pinfunction "XTAL_OUT/27_XTAL_OUT/27") (pintype "bidirectional"))
      (node (ref "Y3") (pin "1") (pinfunction "1_1") (pintype "passive"))
    )
    (net (code "6") (name "Net-(C13-Pad1)") (class "Default")
      (node (ref "C13") (pin "1") (pinfunction "1_1") (pintype "passive"))
      (node (ref "L6") (pin "2") (pinfunction "2_2") (pintype "passive"))
    )
    (net (code "7") (name "Net-(LED1-PadA)") (class "Default")
      (node (ref "LED1") (pin "A") (pinfunction "A_A") (pintype "passive"))
      (node (ref "R9") (pin "2") (pinfunction "2_2") (pintype "passive"))
    )
    (net (code "8") (name "Net-(LED2-PadA)") (class "Default")
      (node (ref "LED2") (pin "A") (pinfunction "A_A") (pintype "passive"))
      (node (ref "R8") (pin "2") (pinfunction "2_2") (pintype "passive"))
    )
    (net (code "9") (name "Net-(LED4-PadA)") (class "Default")
      (node (ref "LED4") (pin "A") (pinfunction "A_A") (pintype "passive"))
      (node (ref "R17") (pin "2") (pinfunction "2_2") (pintype "passive"))
    )
    (net (code "10") (name "Net-(R1-Pad1)") (class "Default")
      (node (ref "R1") (pin "1") (pinfunction "1_1") (pintype "passive"))
      (node (ref "U$6") (pin "RES12K/31") (pinfunction "RES12K/31_RES12K/31") (pintype "bidirectional"))
    )
    (net (code "11") (name "Net-(R5-Pad2)") (class "Default")
      (node (ref "R5") (pin "2") (pinfunction "2_2") (pintype "passive"))
      (node (ref "U$6") (pin "MTCK/12") (pinfunction "MTCK/12_MTCK/12") (pintype "bidirectional"))
    )
    (net (code "12") (name "Net-(R18-Pad2)") (class "Default")
      (node (ref "R18") (pin "2") (pinfunction "2_2") (pintype "passive"))
      (node (ref "U$6") (pin "SD_CLK/21") (pinfunction "SD_CLK/21_SD_CLK/21") (pintype "bidirectional"))
    )
    (net (code "13") (name "Net-(R25-Pad2)") (class "Default")
      (node (ref "R25") (pin "2") (pinfunction "2_2") (pintype "passive"))
      (node (ref "U$8") (pin "G") (pinfunction "G_G") (pintype "bidirectional"))
    )
    (net (code "14") (name "Net-(R26-Pad2)") (class "Default")
      (node (ref "R26") (pin "2") (pinfunction "2_2") (pintype "passive"))
      (node (ref "U$8") (pin "R") (pinfunction "R_R") (pintype "bidirectional"))
    )
    (net (code "15") (name "Net-(R27-Pad2)") (class "Default")
      (node (ref "R27") (pin "2") (pinfunction "2_2") (pintype "passive"))
      (node (ref "U$8") (pin "B") (pinfunction "B_B") (pintype "bidirectional"))
    )
    (net (code "16") (name "Net-(R28-Pad2)") (class "Default")
      (node (ref "R28") (pin "2") (pinfunction "2_2") (pintype "passive"))
      (node (ref "U$11") (pin "B") (pinfunction "B_B") (pintype "bidirectional"))
    )
    (net (code "17") (name "Net-(R29-Pad2)") (class "Default")
      (node (ref "R29") (pin "2") (pinfunction "2_2") (pintype "passive"))
      (node (ref "U$11") (pin "R") (pinfunction "R_R") (pintype "bidirectional"))
    )
    (net (code "18") (name "Net-(R30-Pad2)") (class "Default")
      (node (ref "R30") (pin "2") (pinfunction "2_2") (pintype "passive"))
      (node (ref "U$11") (pin "G") (pinfunction "G_G") (pintype "bidirectional"))
    )
    (net (code "19") (name "Net-(R31-Pad2)") (class "Default")
      (node (ref "R31") (pin "2") (pinfunction "2_2") (pintype "passive"))
      (node (ref "U$13") (pin "B") (pinfunction "B_B") (pintype "bidirectional"))
    )
    (net (code "20") (name "Net-(R32-Pad2)") (class "Default")
      (node (ref "R32") (pin "2") (pinfunction "2_2") (pintype "passive"))
      (node (ref "U$13") (pin "R") (pinfunction "R_R") (pintype "bidirectional"))
    )
    (net (code "21") (name "Net-(R33-Pad2)") (class "Default")
      (node (ref "R33") (pin "2") (pinfunction "2_2") (pintype "passive"))
      (node (ref "U$13") (pin "G") (pinfunction "G_G") (pintype "bidirectional"))
    )
    (net (code "22") (name "Net-(R34-Pad2)") (class "Default")
      (node (ref "R34") (pin "2") (pinfunction "2_2") (pintype "passive"))
      (node (ref "U$14") (pin "B") (pinfunction "B_B") (pintype "bidirectional"))
    )
    (net (code "23") (name "Net-(R35-Pad2)") (class "Default")
      (node (ref "R35") (pin "2") (pinfunction "2_2") (pintype "passive"))
      (node (ref "U$14") (pin "R") (pinfunction "R_R") (pintype "bidirectional"))
    )
    (net (code "24") (name "Net-(R36-Pad2)") (class "Default")
      (node (ref "R36") (pin "2") (pinfunction "2_2") (pintype "passive"))
      (node (ref "U$14") (pin "G") (pinfunction "G_G") (pintype "bidirectional"))
    )
    (net (code "25") (name "Net-(R37-Pad2)") (class "Default")
      (node (ref "R37") (pin "2") (pinfunction "2_2") (pintype "passive"))
      (node (ref "U$15") (pin "B") (pinfunction "B_B") (pintype "bidirectional"))
    )
    (net (code "26") (name "Net-(R38-Pad2)") (class "Default")
      (node (ref "R38") (pin "2") (pinfunction "2_2") (pintype "passive"))
      (node (ref "U$15") (pin "R") (pinfunction "R_R") (pintype "bidirectional"))
    )
    (net (code "27") (name "Net-(R39-Pad2)") (class "Default")
      (node (ref "R39") (pin "2") (pinfunction "2_2") (pintype "passive"))
      (node (ref "U$15") (pin "G") (pinfunction "G_G") (pintype "bidirectional"))
    )
    (net (code "28") (name "Net-(R40-Pad2)") (class "Default")
      (node (ref "R40") (pin "2") (pinfunction "2_2") (pintype "passive"))
      (node (ref "U$16") (pin "B") (pinfunction "B_B") (pintype "bidirectional"))
    )
    (net (code "29") (name "Net-(R41-Pad2)") (class "Default")
      (node (ref "R41") (pin "2") (pinfunction "2_2") (pintype "passive"))
      (node (ref "U$16") (pin "R") (pinfunction "R_R") (pintype "bidirectional"))
    )
    (net (code "30") (name "Net-(R42-Pad2)") (class "Default")
      (node (ref "R42") (pin "2") (pinfunction "2_2") (pintype "passive"))
      (node (ref "U$16") (pin "G") (pinfunction "G_G") (pintype "bidirectional"))
    )
    (net (code "31") (name "Net-(R43-Pad2)") (class "Default")
      (node (ref "R43") (pin "2") (pinfunction "2_2") (pintype "passive"))
      (node (ref "U$17") (pin "B") (pinfunction "B_B") (pintype "bidirectional"))
    )
    (net (code "32") (name "Net-(R44-Pad2)") (class "Default")
      (node (ref "R44") (pin "2") (pinfunction "2_2") (pintype "passive"))
      (node (ref "U$17") (pin "R") (pinfunction "R_R") (pintype "bidirectional"))
    )
    (net (code "33") (name "Net-(R45-Pad2)") (class "Default")
      (node (ref "R45") (pin "2") (pinfunction "2_2") (pintype "passive"))
      (node (ref "U$17") (pin "G") (pinfunction "G_G") (pintype "bidirectional"))
    )
    (net (code "34") (name "Net-(R46-Pad2)") (class "Default")
      (node (ref "R46") (pin "2") (pinfunction "2_2") (pintype "passive"))
      (node (ref "U$18") (pin "B") (pinfunction "B_B") (pintype "bidirectional"))
    )
    (net (code "35") (name "Net-(R47-Pad2)") (class "Default")
      (node (ref "R47") (pin "2") (pinfunction "2_2") (pintype "passive"))
      (node (ref "U$18") (pin "R") (pinfunction "R_R") (pintype "bidirectional"))
    )
    (net (code "36") (name "Net-(R48-Pad2)") (class "Default")
      (node (ref "R48") (pin "2") (pinfunction "2_2") (pintype "passive"))
      (node (ref "U$18") (pin "G") (pinfunction "G_G") (pintype "bidirectional"))
    )
    (net (code "37") (name "Net-(R51-Pad2)") (class "Default")
      (node (ref "R51") (pin "2") (pinfunction "2_2") (pintype "passive"))
      (node (ref "U$6") (pin "MTDO/13") (pinfunction "MTDO/13_MTDO/13") (pintype "bidirectional"))
    )
    (net (code "38") (name "Net-(S1-P)") (class "Default")
      (node (ref "JP5") (pin "2") (pinfunction "2_2") (pintype "passive"))
      (node (ref "S1") (pin "2") (pinfunction "P_2") (pintype "passive"))
    )
    (net (code "39") (name "Net-(U$1-SIGNAL)") (class "Default")
      (node (ref "C6") (pin "1") (pinfunction "1_1") (pintype "passive"))
      (node (ref "L7") (pin "1") (pinfunction "1_1") (pintype "passive"))
      (node (ref "U$1") (pin "FEED") (pinfunction "SIGNAL_FEED") (pintype "bidirectional"))
    )
    (net (code "40") (name "Net-(U$2-SIGNAL)") (class "Default")
      (node (ref "C12") (pin "1") (pinfunction "1_1") (pintype "passive"))
      (node (ref "C13") (pin "2") (pinfunction "2_2") (pintype "passive"))
      (node (ref "U$2") (pin "FEED") (pinfunction "SIGNAL_FEED") (pintype "bidirectional"))
    )
    (net (code "41") (name "Net-(U$3-CLK)") (class "Default")
      (node (ref "R18") (pin "1") (pinfunction "1_1") (pintype "passive"))
      (node (ref "U$3") (pin "6") (pinfunction "CLK_6") (pintype "bidirectional"))
    )
    (net (code "42") (name "Net-(U$3-CS#)") (class "Default")
      (node (ref "U$3") (pin "1") (pinfunction "CS#_1") (pintype "bidirectional"))
      (node (ref "U$6") (pin "SD_CMD/20") (pinfunction "SD_CMD/20_SD_CMD/20") (pintype "bidirectional"))
    )
    (net (code "43") (name "Net-(U$3-DIO)") (class "Default")
      (node (ref "U$3") (pin "5") (pinfunction "DIO_5") (pintype "bidirectional"))
      (node (ref "U$6") (pin "SD_DATA_1/23") (pinfunction "SD_DATA_1/23_SD_DATA_1/23") (pintype "bidirectional"))
    )
    (net (code "44") (name "Net-(U$3-DO)") (class "Default")
      (node (ref "U$3") (pin "2") (pinfunction "DO_2") (pintype "bidirectional"))
      (node (ref "U$6") (pin "SD_DATA_0/22") (pinfunction "SD_DATA_0/22_SD_DATA_0/22") (pintype "bidirectional"))
    )
    (net (code "45") (name "Net-(U$3-HOLD#)") (class "Default")
      (node (ref "U$3") (pin "7") (pinfunction "HOLD#_7") (pintype "bidirectional"))
      (node (ref "U$6") (pin "SD_DATA_2/18") (pinfunction "SD_DATA_2/18_SD_DATA_2/18") (pintype "bidirectional"))
    )
    (net (code "46") (name "Net-(U$3-WP#)") (class "Default")
      (node (ref "U$3") (pin "3") (pinfunction "WP#_3") (pintype "bidirectional"))
      (node (ref "U$6") (pin "SD_DATA_3/19") (pinfunction "SD_DATA_3/19_SD_DATA_3/19") (pintype "bidirectional"))
    )
    (net (code "47") (name "Net-(U$4-ANT1{slash}12)") (class "Default")
      (node (ref "L2") (pin "1") (pinfunction "1_1") (pintype "passive"))
      (node (ref "L5") (pin "2") (pinfunction "2_2") (pintype "passive"))
      (node (ref "U$4") (pin "12") (pinfunction "ANT1/12_12") (pintype "bidirectional"))
    )
    (net (code "48") (name "Net-(U$4-ANT2{slash}13)") (class "Default")
      (node (ref "L5") (pin "1") (pinfunction "1_1") (pintype "passive"))
      (node (ref "L6") (pin "1") (pinfunction "1_1") (pintype "passive"))
      (node (ref "U$4") (pin "13") (pinfunction "ANT2/13_13") (pintype "bidirectional"))
    )
    (net (code "49") (name "Net-(U$4-DVDD{slash}19)") (class "Default")
      (node (ref "C8") (pin "2") (pinfunction "2_2") (pintype "passive"))
      (node (ref "U$4") (pin "19") (pinfunction "DVDD/19_19") (pintype "bidirectional"))
    )
    (net (code "50") (name "Net-(U$4-IREF{slash}16)") (class "Default")
      (node (ref "R12") (pin "1") (pinfunction "1_1") (pintype "passive"))
      (node (ref "U$4") (pin "16") (pinfunction "IREF/16_16") (pintype "bidirectional"))
    )
    (net (code "51") (name "Net-(U$4-VDD_PA{slash}11)") (class "Default")
      (node (ref "C10") (pin "1") (pinfunction "1_1") (pintype "passive"))
      (node (ref "C9") (pin "1") (pinfunction "1_1") (pintype "passive"))
      (node (ref "L2") (pin "2") (pinfunction "2_2") (pintype "passive"))
      (node (ref "U$4") (pin "11") (pinfunction "VDD_PA/11_11") (pintype "bidirectional"))
    )
    (net (code "52") (name "Net-(U$4-XC1{slash}10)") (class "Default")
      (node (ref "C15") (pin "1") (pinfunction "1_1") (pintype "passive"))
      (node (ref "R11") (pin "2") (pinfunction "2_2") (pintype "passive"))
      (node (ref "U$4") (pin "10") (pinfunction "XC1/10_10") (pintype "bidirectional"))
      (node (ref "Y4") (pin "3") (pinfunction "2_3") (pintype "passive"))
    )
    (net (code "53") (name "Net-(U$4-XC2{slash}9)") (class "Default")
      (node (ref "C14") (pin "1") (pinfunction "1_1") (pintype "passive"))
      (node (ref "R11") (pin "1") (pinfunction "1_1") (pintype "passive"))
      (node (ref "U$4") (pin "9") (pinfunction "XC2/9_9") (pintype "bidirectional"))
      (node (ref "Y4") (pin "1") (pinfunction "1_1") (pintype "passive"))
    )
    (net (code "54") (name "Net-(U$7-NC{slash}TDI)") (class "Default")
      (node (ref "R52") (pin "2") (pinfunction "2_2") (pintype "passive"))
      (node (ref "U$7") (pin "8") (pinfunction "NC/TDI_8") (pintype "bidirectional"))
      (node (ref "U1") (pin "23") (pinfunction "PTA1_23") (pintype "bidirectional"))
    )
    (net (code "55") (name "Net-(U$7-SWO{slash}TDO)") (class "Default")
      (node (ref "U$7") (pin "6") (pinfunction "SWO/TDO_6") (pintype "bidirectional"))
      (node (ref "U1") (pin "24") (pinfunction "PTA2_24") (pintype "bidirectional"))
    )
    (net (code "56") (name "Net-(U$7-~{RESET})") (class "Default")
      (node (ref "R53") (pin "2") (pinfunction "2_2") (pintype "passive"))
      (node (ref "U$7") (pin "10") (pinfunction "~{RESET}_10") (pintype "bidirectional"))
      (node (ref "U1") (pin "34") (pinfunction "RESET_B_34") (pintype "bidirectional"))
    )
    (net (code "57") (name "Net-(U$20-A0)") (class "Default")
      (node (ref "R21") (pin "1") (pinfunction "1_1") (pintype "passive"))
      (node (ref "U$20") (pin "22") (pinfunction "A0_22") (pintype "bidirectional"))
    )
    (net (code "58") (name "Net-(U$20-A1)") (class "Default")
      (node (ref "R20") (pin "1") (pinfunction "1_1") (pintype "passive"))
      (node (ref "U$20") (pin "23") (pinfunction "A1_23") (pintype "bidirectional"))
    )
    (net (code "59") (name "Net-(U$20-A2)") (class "Default")
      (node (ref "R19") (pin "1") (pinfunction "1_1") (pintype "passive"))
      (node (ref "U$20") (pin "24") (pinfunction "A2_24") (pintype "bidirectional"))
    )
    (net (code "60") (name "Net-(U$20-LED0)") (class "Default")
      (node (ref "R26") (pin "1") (pinfunction "1_1") (pintype "passive"))
      (node (ref "U$20") (pin "1") (pinfunction "LED0_1") (pintype "bidirectional"))
    )
    (net (code "61") (name "Net-(U$20-LED1)") (class "Default")
      (node (ref "R25") (pin "1") (pinfunction "1_1") (pintype "passive"))
      (node (ref "U$20") (pin "2") (pinfunction "LED1_2") (pintype "bidirectional"))
    )
    (net (code "62") (name "Net-(U$20-LED2)") (class "Default")
      (node (ref "R27") (pin "1") (pinfunction "1_1") (pintype "passive"))
      (node (ref "U$20") (pin "3") (pinfunction "LED2_3") (pintype "bidirectional"))
    )
    (net (code "63") (name "Net-(U$20-LED3)") (class "Default")
      (node (ref "R29") (pin "1") (pinfunction "1_1") (pintype "passive"))
      (node (ref "U$20") (pin "4") (pinfunction "LED3_4") (pintype "bidirectional"))
    )
    (net (code "64") (name "Net-(U$20-LED4)") (class "Default")
      (node (ref "R30") (pin "1") (pinfunction "1_1") (pintype "passive"))
      (node (ref "U$20") (pin "5") (pinfunction "LED4_5") (pintype "bidirectional"))
    )
    (net (code "65") (name "Net-(U$20-LED5)") (class "Default")
      (node (ref "R28") (pin "1") (pinfunction "1_1") (pintype "passive"))
      (node (ref "U$20") (pin "6") (pinfunction "LED5_6") (pintype "bidirectional"))
    )
    (net (code "66") (name "Net-(U$20-LED6)") (class "Default")
      (node (ref "R32") (pin "1") (pinfunction "1_1") (pintype "passive"))
      (node (ref "U$20") (pin "7") (pinfunction "LED6_7") (pintype "bidirectional"))
    )
    (net (code "67") (name "Net-(U$20-LED7)") (class "Default")
      (node (ref "R33") (pin "1") (pinfunction "1_1") (pintype "passive"))
      (node (ref "U$20") (pin "8") (pinfunction "LED7_8") (pintype "bidirectional"))
    )
    (net (code "68") (name "Net-(U$20-LED8)") (class "Default")
      (node (ref "R31") (pin "1") (pinfunction "1_1") (pintype "passive"))
      (node (ref "U$20") (pin "10") (pinfunction "LED8_10") (pintype "bidirectional"))
    )
    (net (code "69") (name "Net-(U$20-LED9)") (class "Default")
      (node (ref "R35") (pin "1") (pinfunction "1_1") (pintype "passive"))
      (node (ref "U$20") (pin "11") (pinfunction "LED9_11") (pintype "bidirectional"))
    )
    (net (code "70") (name "Net-(U$20-LED10)") (class "Default")
      (node (ref "R36") (pin "1") (pinfunction "1_1") (pintype "passive"))
      (node (ref "U$20") (pin "12") (pinfunction "LED10_12") (pintype "bidirectional"))
    )
    (net (code "71") (name "Net-(U$20-LED11)") (class "Default")
      (node (ref "R34") (pin "1") (pinfunction "1_1") (pintype "passive"))
      (node (ref "U$20") (pin "13") (pinfunction "LED11_13") (pintype "bidirectional"))
    )
    (net (code "72") (name "Net-(U$21-A0)") (class "Default")
      (node (ref "R22") (pin "1") (pinfunction "1_1") (pintype "passive"))
      (node (ref "U$21") (pin "22") (pinfunction "A0_22") (pintype "bidirectional"))
    )
    (net (code "73") (name "Net-(U$21-A1)") (class "Default")
      (node (ref "R23") (pin "1") (pinfunction "1_1") (pintype "passive"))
      (node (ref "U$21") (pin "23") (pinfunction "A1_23") (pintype "bidirectional"))
    )
    (net (code "74") (name "Net-(U$21-A2)") (class "Default")
      (node (ref "R24") (pin "1") (pinfunction "1_1") (pintype "passive"))
      (node (ref "U$21") (pin "24") (pinfunction "A2_24") (pintype "bidirectional"))
    )
    (net (code "75") (name "Net-(U$21-LED0)") (class "Default")
      (node (ref "R38") (pin "1") (pinfunction "1_1") (pintype "passive"))
      (node (ref "U$21") (pin "1") (pinfunction "LED0_1") (pintype "bidirectional"))
    )
    (net (code "76") (name "Net-(U$21-LED1)") (class "Default")
      (node (ref "R39") (pin "1") (pinfunction "1_1") (pintype "passive"))
      (node (ref "U$21") (pin "2") (pinfunction "LED1_2") (pintype "bidirectional"))
    )
    (net (code "77") (name "Net-(U$21-LED2)") (class "Default")
      (node (ref "R37") (pin "1") (pinfunction "1_1") (pintype "passive"))
      (node (ref "U$21") (pin "3") (pinfunction "LED2_3") (pintype "bidirectional"))
    )
    (net (code "78") (name "Net-(U$21-LED3)") (class "Default")
      (node (ref "R41") (pin "1") (pinfunction "1_1") (pintype "passive"))
      (node (ref "U$21") (pin "4") (pinfunction "LED3_4") (pintype "bidirectional"))
    )
    (net (code "79") (name "Net-(U$21-LED4)") (class "Default")
      (node (ref "R42") (pin "1") (pinfunction "1_1") (pintype "passive"))
      (node (ref "U$21") (pin "5") (pinfunction "LED4_5") (pintype "bidirectional"))
    )
    (net (code "80") (name "Net-(U$21-LED5)") (class "Default")
      (node (ref "R40") (pin "1") (pinfunction "1_1") (pintype "passive"))
      (node (ref "U$21") (pin "6") (pinfunction "LED5_6") (pintype "bidirectional"))
    )
    (net (code "81") (name "Net-(U$21-LED6)") (class "Default")
      (node (ref "R44") (pin "1") (pinfunction "1_1") (pintype "passive"))
      (node (ref "U$21") (pin "7") (pinfunction "LED6_7") (pintype "bidirectional"))
    )
    (net (code "82") (name "Net-(U$21-LED7)") (class "Default")
      (node (ref "R45") (pin "1") (pinfunction "1_1") (pintype "passive"))
      (node (ref "U$21") (pin "8") (pinfunction "LED7_8") (pintype "bidirectional"))
    )
    (net (code "83") (name "Net-(U$21-LED8)") (class "Default")
      (node (ref "R43") (pin "1") (pinfunction "1_1") (pintype "passive"))
      (node (ref "U$21") (pin "10") (pinfunction "LED8_10") (pintype "bidirectional"))
    )
    (net (code "84") (name "Net-(U$21-LED9)") (class "Default")
      (node (ref "R47") (pin "1") (pinfunction "1_1") (pintype "passive"))
      (node (ref "U$21") (pin "11") (pinfunction "LED9_11") (pintype "bidirectional"))
    )
    (net (code "85") (name "Net-(U$21-LED10)") (class "Default")
      (node (ref "R48") (pin "1") (pinfunction "1_1") (pintype "passive"))
      (node (ref "U$21") (pin "12") (pinfunction "LED10_12") (pintype "bidirectional"))
    )
    (net (code "86") (name "Net-(U$21-LED11)") (class "Default")
      (node (ref "R46") (pin "1") (pinfunction "1_1") (pintype "passive"))
      (node (ref "U$21") (pin "13") (pinfunction "LED11_13") (pintype "bidirectional"))
    )
    (net (code "87") (name "Net-(U1-EXTAL32)") (class "Default")
      (node (ref "C32") (pin "2") (pinfunction "2_2") (pintype "passive"))
      (node (ref "U1") (pin "20") (pinfunction "EXTAL32_20") (pintype "bidirectional"))
      (node (ref "Y1") (pin "P$1") (pinfunction "1_P$1") (pintype "passive"))
    )
    (net (code "88") (name "Net-(U1-PTA18)") (class "Default")
      (node (ref "C29") (pin "2") (pinfunction "2_2") (pintype "passive"))
      (node (ref "U1") (pin "32") (pinfunction "PTA18_32") (pintype "bidirectional"))
      (node (ref "Y2") (pin "3") (pinfunction "2_3") (pintype "passive"))
    )
    (net (code "89") (name "Net-(U1-PTA19)") (class "Default")
      (node (ref "C30") (pin "2") (pinfunction "2_2") (pintype "passive"))
      (node (ref "U1") (pin "33") (pinfunction "PTA19_33") (pintype "bidirectional"))
      (node (ref "Y2") (pin "1") (pinfunction "1_1") (pintype "passive"))
    )
    (net (code "90") (name "Net-(U1-PTD6)") (class "Default")
      (node (ref "R8") (pin "1") (pinfunction "1_1") (pintype "passive"))
      (node (ref "U1") (pin "63") (pinfunction "PTD6_63") (pintype "bidirectional"))
    )
    (net (code "91") (name "Net-(U1-PTD7)") (class "Default")
      (node (ref "R17") (pin "1") (pinfunction "1_1") (pintype "passive"))
      (node (ref "U1") (pin "64") (pinfunction "PTD7_64") (pintype "bidirectional"))
    )
    (net (code "92") (name "Net-(U1-VDDA)") (class "Default")
      (node (ref "C17") (pin "1") (pinfunction "1_1") (pintype "passive"))
      (node (ref "L3") (pin "1") (pinfunction "1_1") (pintype "passive"))
      (node (ref "R16") (pin "1") (pinfunction "1_1") (pintype "passive"))
      (node (ref "U1") (pin "13") (pinfunction "VDDA_13") (pintype "bidirectional"))
    )
    (net (code "93") (name "Net-(U1-VREFH)") (class "Default")
      (node (ref "C11") (pin "1") (pinfunction "1_1") (pintype "passive"))
      (node (ref "R16") (pin "2") (pinfunction "2_2") (pintype "passive"))
      (node (ref "U1") (pin "14") (pinfunction "VREFH_14") (pintype "bidirectional"))
    )
    (net (code "94") (name "Net-(U1-VREFL)") (class "Default")
      (node (ref "C11") (pin "2") (pinfunction "2_2") (pintype "passive"))
      (node (ref "C16") (pin "2") (pinfunction "2_2") (pintype "passive"))
      (node (ref "C17") (pin "2") (pinfunction "2_2") (pintype "passive"))
      (node (ref "L4") (pin "2") (pinfunction "2_2") (pintype "passive"))
      (node (ref "U1") (pin "15") (pinfunction "VREFL_15") (pintype "bidirectional"))
      (node (ref "U1") (pin "16") (pinfunction "VSSA_16") (pintype "bidirectional"))
    )
    (net (code "95") (name "Net-(U1-VREF_OUT)") (class "Default")
      (node (ref "C16") (pin "1") (pinfunction "1_1") (pintype "passive"))
      (node (ref "U1") (pin "17") (pinfunction "VREF_OUT_17") (pintype "bidirectional"))
    )
    (net (code "96") (name "Net-(U1-XTAL32)") (class "Default")
      (node (ref "C31") (pin "2") (pinfunction "2_2") (pintype "passive"))
      (node (ref "U1") (pin "19") (pinfunction "XTAL32_19") (pintype "bidirectional"))
      (node (ref "Y1") (pin "P$2") (pinfunction "2_P$2") (pintype "passive"))
    )
    (net (code "97") (name "Net-(U2-FB)") (class "Default")
      (node (ref "R6") (pin "2") (pinfunction "2_2") (pintype "passive"))
      (node (ref "R7") (pin "1") (pinfunction "1_1") (pintype "passive"))
      (node (ref "U2") (pin "10") (pinfunction "FB_10") (pintype "passive"))
    )
    (net (code "98") (name "Net-(U2-L)") (class "Default")
      (node (ref "L1") (pin "1") (pinfunction "1_1") (pintype "passive"))
      (node (ref "U2") (pin "3") (pinfunction "L_3") (pintype "passive"))
    )
    (net (code "99") (name "Net-(U2-UVLO)") (class "Default")
      (node (ref "C2") (pin "2") (pinfunction "2_2") (pintype "passive"))
      (node (ref "R3") (pin "1") (pinfunction "1_1") (pintype "passive"))
      (node (ref "R4") (pin "2") (pinfunction "2_2") (pintype "passive"))
      (node (ref "U2") (pin "7") (pinfunction "UVLO_7") (pintype "passive"))
    )
    (net (code "100") (name "Net-(U2-VAUX)") (class "Default")
      (node (ref "C4") (pin "1") (pinfunction "1_1") (pintype "passive"))
      (node (ref "U2") (pin "1") (pinfunction "VAUX_1") (pintype "passive"))
    )
    (net (code "101") (name "Net-(U3-REGOUT)") (class "Default")
      (node (ref "C27") (pin "2") (pinfunction "2_2") (pintype "passive"))
      (node (ref "U3") (pin "10") (pinfunction "REGOUT_10") (pintype "bidirectional"))
    )
    (net (code "102") (name "Net-(Y3-2)") (class "Default")
      (node (ref "C23") (pin "1") (pinfunction "1_1") (pintype "passive"))
      (node (ref "U$6") (pin "XTAL_IN/28") (pinfunction "XTAL_IN/28_XTAL_IN/28") (pintype "bidirectional"))
      (node (ref "Y3") (pin "3") (pinfunction "2_3") (pintype "passive"))
    )
    (net (code "103") (name "PS") (class "Default")
      (node (ref "R2") (pin "2") (pinfunction "2_2") (pintype "passive"))
      (node (ref "U2") (pin "8") (pinfunction "PS_8") (pintype "input"))
    )
    (net (code "104") (name "PTA0") (class "Default")
      (node (ref "R50") (pin "2") (pinfunction "2_2") (pintype "passive"))
      (node (ref "U$7") (pin "4") (pinfunction "SWDCLK/TCK_4") (pintype "bidirectional"))
      (node (ref "U1") (pin "22") (pinfunction "PTA0_22") (pintype "bidirectional"))
    )
    (net (code "105") (name "PTA3") (class "Default")
      (node (ref "R49") (pin "2") (pinfunction "2_2") (pintype "passive"))
      (node (ref "U$7") (pin "2") (pinfunction "SWDIO/TMS_2") (pintype "bidirectional"))
      (node (ref "U1") (pin "25") (pinfunction "PTA3_25") (pintype "bidirectional"))
    )
    (net (code "106") (name "PTB0") (class "Default")
      (node (ref "U1") (pin "35") (pinfunction "PTB0_35") (pintype "bidirectional"))
      (node (ref "U3") (pin "12") (pinfunction "INT_12") (pintype "bidirectional"))
    )
    (net (code "107") (name "PTB1") (class "Default")
      (node (ref "U1") (pin "36") (pinfunction "PTB1_36") (pintype "bidirectional"))
      (node (ref "U3") (pin "11") (pinfunction "FSYNC_11") (pintype "bidirectional"))
    )
    (net (code "108") (name "PTB16") (class "Default")
      (node (ref "U$6") (pin "U0TXD/26") (pinfunction "U0TXD/26_U0TXD/26") (pintype "bidirectional"))
      (node (ref "U1") (pin "39") (pinfunction "PTB16_39") (pintype "bidirectional"))
    )
    (net (code "109") (name "PTB17") (class "Default")
      (node (ref "U$6") (pin "U0RXD/25") (pinfunction "U0RXD/25_U0RXD/25") (pintype "bidirectional"))
      (node (ref "U1") (pin "40") (pinfunction "PTB17_40") (pintype "bidirectional"))
    )
    (net (code "110") (name "PTB18") (class "Default")
      (node (ref "U$6") (pin "GPIO0/15") (pinfunction "GPIO0/15_GPIO0/15") (pintype "bidirectional"))
      (node (ref "U1") (pin "41") (pinfunction "PTB18_41") (pintype "bidirectional"))
    )
    (net (code "111") (name "PTB19") (class "Default")
      (node (ref "U$6") (pin "GPIO2/14") (pinfunction "GPIO2/14_GPIO2/14") (pintype "bidirectional"))
      (node (ref "U1") (pin "42") (pinfunction "PTB19_42") (pintype "bidirectional"))
    )
    (net (code "112") (name "PTC0") (class "Default")
      (node (ref "R15") (pin "1") (pinfunction "1_1") (pintype "passive"))
      (node (ref "U$6") (pin "EXT_RSTB/32") (pinfunction "EXT_RSTB/32_EXT_RSTB/32") (pintype "bidirectional"))
      (node (ref "U1") (pin "43") (pinfunction "PTC0_43") (pintype "bidirectional"))
    )
    (net (code "113") (name "PTC1") (class "Default")
      (node (ref "U$6") (pin "CHIP_EN/7") (pinfunction "CHIP_EN/7_CHIP_EN/7") (pintype "bidirectional"))
      (node (ref "U1") (pin "44") (pinfunction "PTC1_44") (pintype "bidirectional"))
    )
    (net (code "114") (name "PTC3") (class "Default")
      (node (ref "U$6") (pin "XPD_DCDC/8") (pinfunction "XPD_DCDC/8_XPD_DCDC/8") (pintype "bidirectional"))
      (node (ref "U1") (pin "46") (pinfunction "PTC3_46") (pintype "bidirectional"))
    )
    (net (code "115") (name "PTC4") (class "Default")
      (node (ref "U$4") (pin "2") (pinfunction "CSN/2_2") (pintype "bidirectional"))
      (node (ref "U1") (pin "49") (pinfunction "PTC4_49") (pintype "bidirectional"))
    )
    (net (code "116") (name "PTC5") (class "Default")
      (node (ref "U$4") (pin "3") (pinfunction "SCK/3_3") (pintype "bidirectional"))
      (node (ref "U1") (pin "50") (pinfunction "PTC5_50") (pintype "bidirectional"))
    )
    (net (code "117") (name "PTC6") (class "Default")
      (node (ref "U$4") (pin "4") (pinfunction "MOSI/4_4") (pintype "bidirectional"))
      (node (ref "U1") (pin "51") (pinfunction "PTC6_51") (pintype "bidirectional"))
    )
    (net (code "118") (name "PTC7") (class "Default")
      (node (ref "U$4") (pin "5") (pinfunction "MISO/5_5") (pintype "bidirectional"))
      (node (ref "U1") (pin "52") (pinfunction "PTC7_52") (pintype "bidirectional"))
    )
    (net (code "119") (name "PTC8") (class "Default")
      (node (ref "U$4") (pin "6") (pinfunction "IRQ/6_6") (pintype "bidirectional"))
      (node (ref "U1") (pin "53") (pinfunction "PTC8_53") (pintype "bidirectional"))
    )
    (net (code "120") (name "PTC9") (class "Default")
      (node (ref "U$4") (pin "1") (pinfunction "CE/1_1") (pintype "bidirectional"))
      (node (ref "U1") (pin "54") (pinfunction "PTC9_54") (pintype "bidirectional"))
    )
    (net (code "121") (name "PTC10") (class "Default")
      (node (ref "JP1") (pin "12") (pinfunction "12_12") (pintype "passive"))
      (node (ref "U1") (pin "55") (pinfunction "PTC10_55") (pintype "bidirectional"))
    )
    (net (code "122") (name "PTC11") (class "Default")
      (node (ref "JP1") (pin "11") (pinfunction "11_11") (pintype "passive"))
      (node (ref "U1") (pin "56") (pinfunction "PTC11_56") (pintype "bidirectional"))
    )
    (net (code "123") (name "PTD0") (class "Default")
      (node (ref "JP1") (pin "10") (pinfunction "10_10") (pintype "passive"))
      (node (ref "U1") (pin "57") (pinfunction "PTD0_57") (pintype "bidirectional"))
    )
    (net (code "124") (name "PTD1") (class "Default")
      (node (ref "JP1") (pin "9") (pinfunction "9_9") (pintype "passive"))
      (node (ref "U1") (pin "58") (pinfunction "PTD1_58") (pintype "bidirectional"))
    )
    (net (code "125") (name "PTD2") (class "Default")
      (node (ref "JP1") (pin "8") (pinfunction "8_8") (pintype "passive"))
      (node (ref "U1") (pin "59") (pinfunction "PTD2_59") (pintype "bidirectional"))
    )
    (net (code "126") (name "PTD3") (class "Default")
      (node (ref "JP1") (pin "7") (pinfunction "7_7") (pintype "passive"))
      (node (ref "U1") (pin "60") (pinfunction "PTD3_60") (pintype "bidirectional"))
    )
    (net (code "127") (name "PTD4") (class "Default")
      (node (ref "JP1") (pin "6") (pinfunction "6_6") (pintype "passive"))
      (node (ref "U1") (pin "61") (pinfunction "PTD4_61") (pintype "bidirectional"))
    )
    (net (code "128") (name "PTD5") (class "Default")
      (node (ref "JP1") (pin "5") (pinfunction "5_5") (pintype "passive"))
      (node (ref "U1") (pin "62") (pinfunction "PTD5_62") (pintype "bidirectional"))
    )
    (net (code "129") (name "SCL") (class "Default")
      (node (ref "R14") (pin "2") (pinfunction "2_2") (pintype "passive"))
      (node (ref "U$20") (pin "19") (pinfunction "SCL_19") (pintype "bidirectional"))
      (node (ref "U$21") (pin "19") (pinfunction "SCL_19") (pintype "bidirectional"))
      (node (ref "U1") (pin "37") (pinfunction "PTB2_37") (pintype "bidirectional"))
      (node (ref "U3") (pin "23") (pinfunction "SCLK_23") (pintype "bidirectional"))
    )
    (net (code "130") (name "SDA") (class "Default")
      (node (ref "R13") (pin "2") (pinfunction "2_2") (pintype "passive"))
      (node (ref "U$20") (pin "20") (pinfunction "SDA_20") (pintype "bidirectional"))
      (node (ref "U$21") (pin "20") (pinfunction "SDA_20") (pintype "bidirectional"))
      (node (ref "U1") (pin "38") (pinfunction "PTB3_38") (pintype "bidirectional"))
      (node (ref "U3") (pin "24") (pinfunction "SDA/MOSI_24") (pintype "bidirectional"))
    )
    (net (code "131") (name "SOFTPOWER") (class "Default")
      (node (ref "R10") (pin "1") (pinfunction "1_1") (pintype "passive"))
      (node (ref "U2") (pin "6") (pinfunction "EN_6") (pintype "input"))
    )
    (net (code "132") (name "USB_D_N") (class "Default")
      (node (ref "U1") (pin "6") (pinfunction "USB0_DM_6") (pintype "bidirectional"))
    )
    (net (code "133") (name "USB_D_P") (class "Default")
      (node (ref "U1") (pin "5") (pinfunction "USB0_DP_5") (pintype "bidirectional"))
    )
    (net (code "134") (name "VCC") (class "Default")
      (node (ref "C1") (pin "1") (pinfunction "1_1") (pintype "passive"))
      (node (ref "C2") (pin "1") (pinfunction "1_1") (pintype "passive"))
      (node (ref "L1") (pin "2") (pinfunction "2_2") (pintype "passive"))
      (node (ref "R10") (pin "2") (pinfunction "2_2") (pintype "passive"))
      (node (ref "R2") (pin "1") (pinfunction "1_1") (pintype "passive"))
      (node (ref "R3") (pin "2") (pinfunction "2_2") (pintype "passive"))
      (node (ref "S1") (pin "1") (pinfunction "O_1") (pintype "passive"))
      (node (ref "U2") (pin "5") (pinfunction "VIN_5") (pintype "power_in"))
    )
    (net (code "135") (name "unconnected-(S1-S-Pad3)") (class "Default")
      (node (ref "S1") (pin "3") (pinfunction "S_3") (pintype "passive"))
    )
    (net (code "136") (name "unconnected-(U$6-PadDVDD{slash}24)") (class "Default")
      (node (ref "U$6") (pin "DVDD/24") (pinfunction "DVDD/24_DVDD/24") (pintype "bidirectional"))
    )
    (net (code "137") (name "unconnected-(U$6-PadMTDI{slash}10)") (class "Default")
      (node (ref "U$6") (pin "MTDI/10") (pinfunction "MTDI/10_MTDI/10") (pintype "bidirectional"))
    )
    (net (code "138") (name "unconnected-(U$6-PadMTMS{slash}9)") (class "Default")
      (node (ref "U$6") (pin "MTMS/9") (pinfunction "MTMS/9_MTMS/9") (pintype "bidirectional"))
    )
    (net (code "139") (name "unconnected-(U$6-PadTOUT{slash}6)") (class "Default")
      (node (ref "U$6") (pin "TOUT/6") (pinfunction "TOUT/6_TOUT/6") (pintype "bidirectional"))
    )
    (net (code "140") (name "unconnected-(U$6-PadVDD_RTC{slash}5)") (class "Default")
      (node (ref "U$6") (pin "VDD_RTC/5") (pinfunction "VDD_RTC/5_VDD_RTC/5") (pintype "bidirectional"))
    )
    (net (code "141") (name "unconnected-(U$6-PadVDD{slash}16)") (class "Default")
      (node (ref "U$6") (pin "VDD/16") (pinfunction "VDD/16_VDD/16") (pintype "bidirectional"))
    )
    (net (code "142") (name "unconnected-(U$20-LED12-Pad14)") (class "Default")
      (node (ref "U$20") (pin "14") (pinfunction "LED12_14") (pintype "bidirectional"))
    )
    (net (code "143") (name "unconnected-(U$20-LED13-Pad15)") (class "Default")
      (node (ref "U$20") (pin "15") (pinfunction "LED13_15") (pintype "bidirectional"))
    )
    (net (code "144") (name "unconnected-(U$20-LED14-Pad16)") (class "Default")
      (node (ref "U$20") (pin "16") (pinfunction "LED14_16") (pintype "bidirectional"))
    )
    (net (code "145") (name "unconnected-(U$20-LED15-Pad17)") (class "Default")
      (node (ref "U$20") (pin "17") (pinfunction "LED15_17") (pintype "bidirectional"))
    )
    (net (code "146") (name "unconnected-(U$20-LED16-Pad18)") (class "Default")
      (node (ref "U$20") (pin "18") (pinfunction "LED16_18") (pintype "bidirectional"))
    )
    (net (code "147") (name "unconnected-(U$21-LED12-Pad14)") (class "Default")
      (node (ref "U$21") (pin "14") (pinfunction "LED12_14") (pintype "bidirectional"))
    )
    (net (code "148") (name "unconnected-(U$21-LED13-Pad15)") (class "Default")
      (node (ref "U$21") (pin "15") (pinfunction "LED13_15") (pintype "bidirectional"))
    )
    (net (code "149") (name "unconnected-(U$21-LED14-Pad16)") (class "Default")
      (node (ref "U$21") (pin "16") (pinfunction "LED14_16") (pintype "bidirectional"))
    )
    (net (code "150") (name "unconnected-(U$21-LED15-Pad17)") (class "Default")
      (node (ref "U$21") (pin "17") (pinfunction "LED15_17") (pintype "bidirectional"))
    )
    (net (code "151") (name "unconnected-(U$21-LED16-Pad18)") (class "Default")
      (node (ref "U$21") (pin "18") (pinfunction "LED16_18") (pintype "bidirectional"))
    )
    (net (code "152") (name "unconnected-(U1-ADC0_DM0-Pad10)") (class "Default")
      (node (ref "U1") (pin "10") (pinfunction "ADC0_DM0_10") (pintype "bidirectional"))
    )
    (net (code "153") (name "unconnected-(U1-ADC0_DM3-Pad12)") (class "Default")
      (node (ref "U1") (pin "12") (pinfunction "ADC0_DM3_12") (pintype "bidirectional"))
    )
    (net (code "154") (name "unconnected-(U1-ADC0_DP0-Pad9)") (class "Default")
      (node (ref "U1") (pin "9") (pinfunction "ADC0_DP0_9") (pintype "bidirectional"))
    )
    (net (code "155") (name "unconnected-(U1-ADC0_DP3-Pad11)") (class "Default")
      (node (ref "U1") (pin "11") (pinfunction "ADC0_DP3_11") (pintype "bidirectional"))
    )
    (net (code "156") (name "unconnected-(U1-DAC0-Pad18)") (class "Default")
      (node (ref "U1") (pin "18") (pinfunction "DAC0_18") (pintype "bidirectional"))
    )
    (net (code "157") (name "unconnected-(U1-PTA4-Pad26)") (class "Default")
      (node (ref "U1") (pin "26") (pinfunction "PTA4_26") (pintype "bidirectional"))
    )
    (net (code "158") (name "unconnected-(U1-PTA5-Pad27)") (class "Default")
      (node (ref "U1") (pin "27") (pinfunction "PTA5_27") (pintype "bidirectional"))
    )
    (net (code "159") (name "unconnected-(U1-PTA12-Pad28)") (class "Default")
      (node (ref "U1") (pin "28") (pinfunction "PTA12_28") (pintype "bidirectional"))
    )
    (net (code "160") (name "unconnected-(U1-PTA13-Pad29)") (class "Default")
      (node (ref "U1") (pin "29") (pinfunction "PTA13_29") (pintype "bidirectional"))
    )
    (net (code "161") (name "unconnected-(U1-PTE0-Pad1)") (class "Default")
      (node (ref "U1") (pin "1") (pinfunction "PTE0_1") (pintype "bidirectional"))
    )
    (net (code "162") (name "unconnected-(U1-PTE1-Pad2)") (class "Default")
      (node (ref "U1") (pin "2") (pinfunction "PTE1_2") (pintype "bidirectional"))
    )
    (net (code "163") (name "unconnected-(U3-AUX_CL-Pad7)") (class "Default")
      (node (ref "U3") (pin "7") (pinfunction "AUX_CL_7") (pintype "bidirectional"))
    )
    (net (code "164") (name "unconnected-(U3-AUX_DA-Pad21)") (class "Default")
      (node (ref "U3") (pin "21") (pinfunction "AUX_DA_21") (pintype "bidirectional"))
    )
  )
)
